# 14.net
KiCad netlist of a schematic drawn in EasyEDA Pro
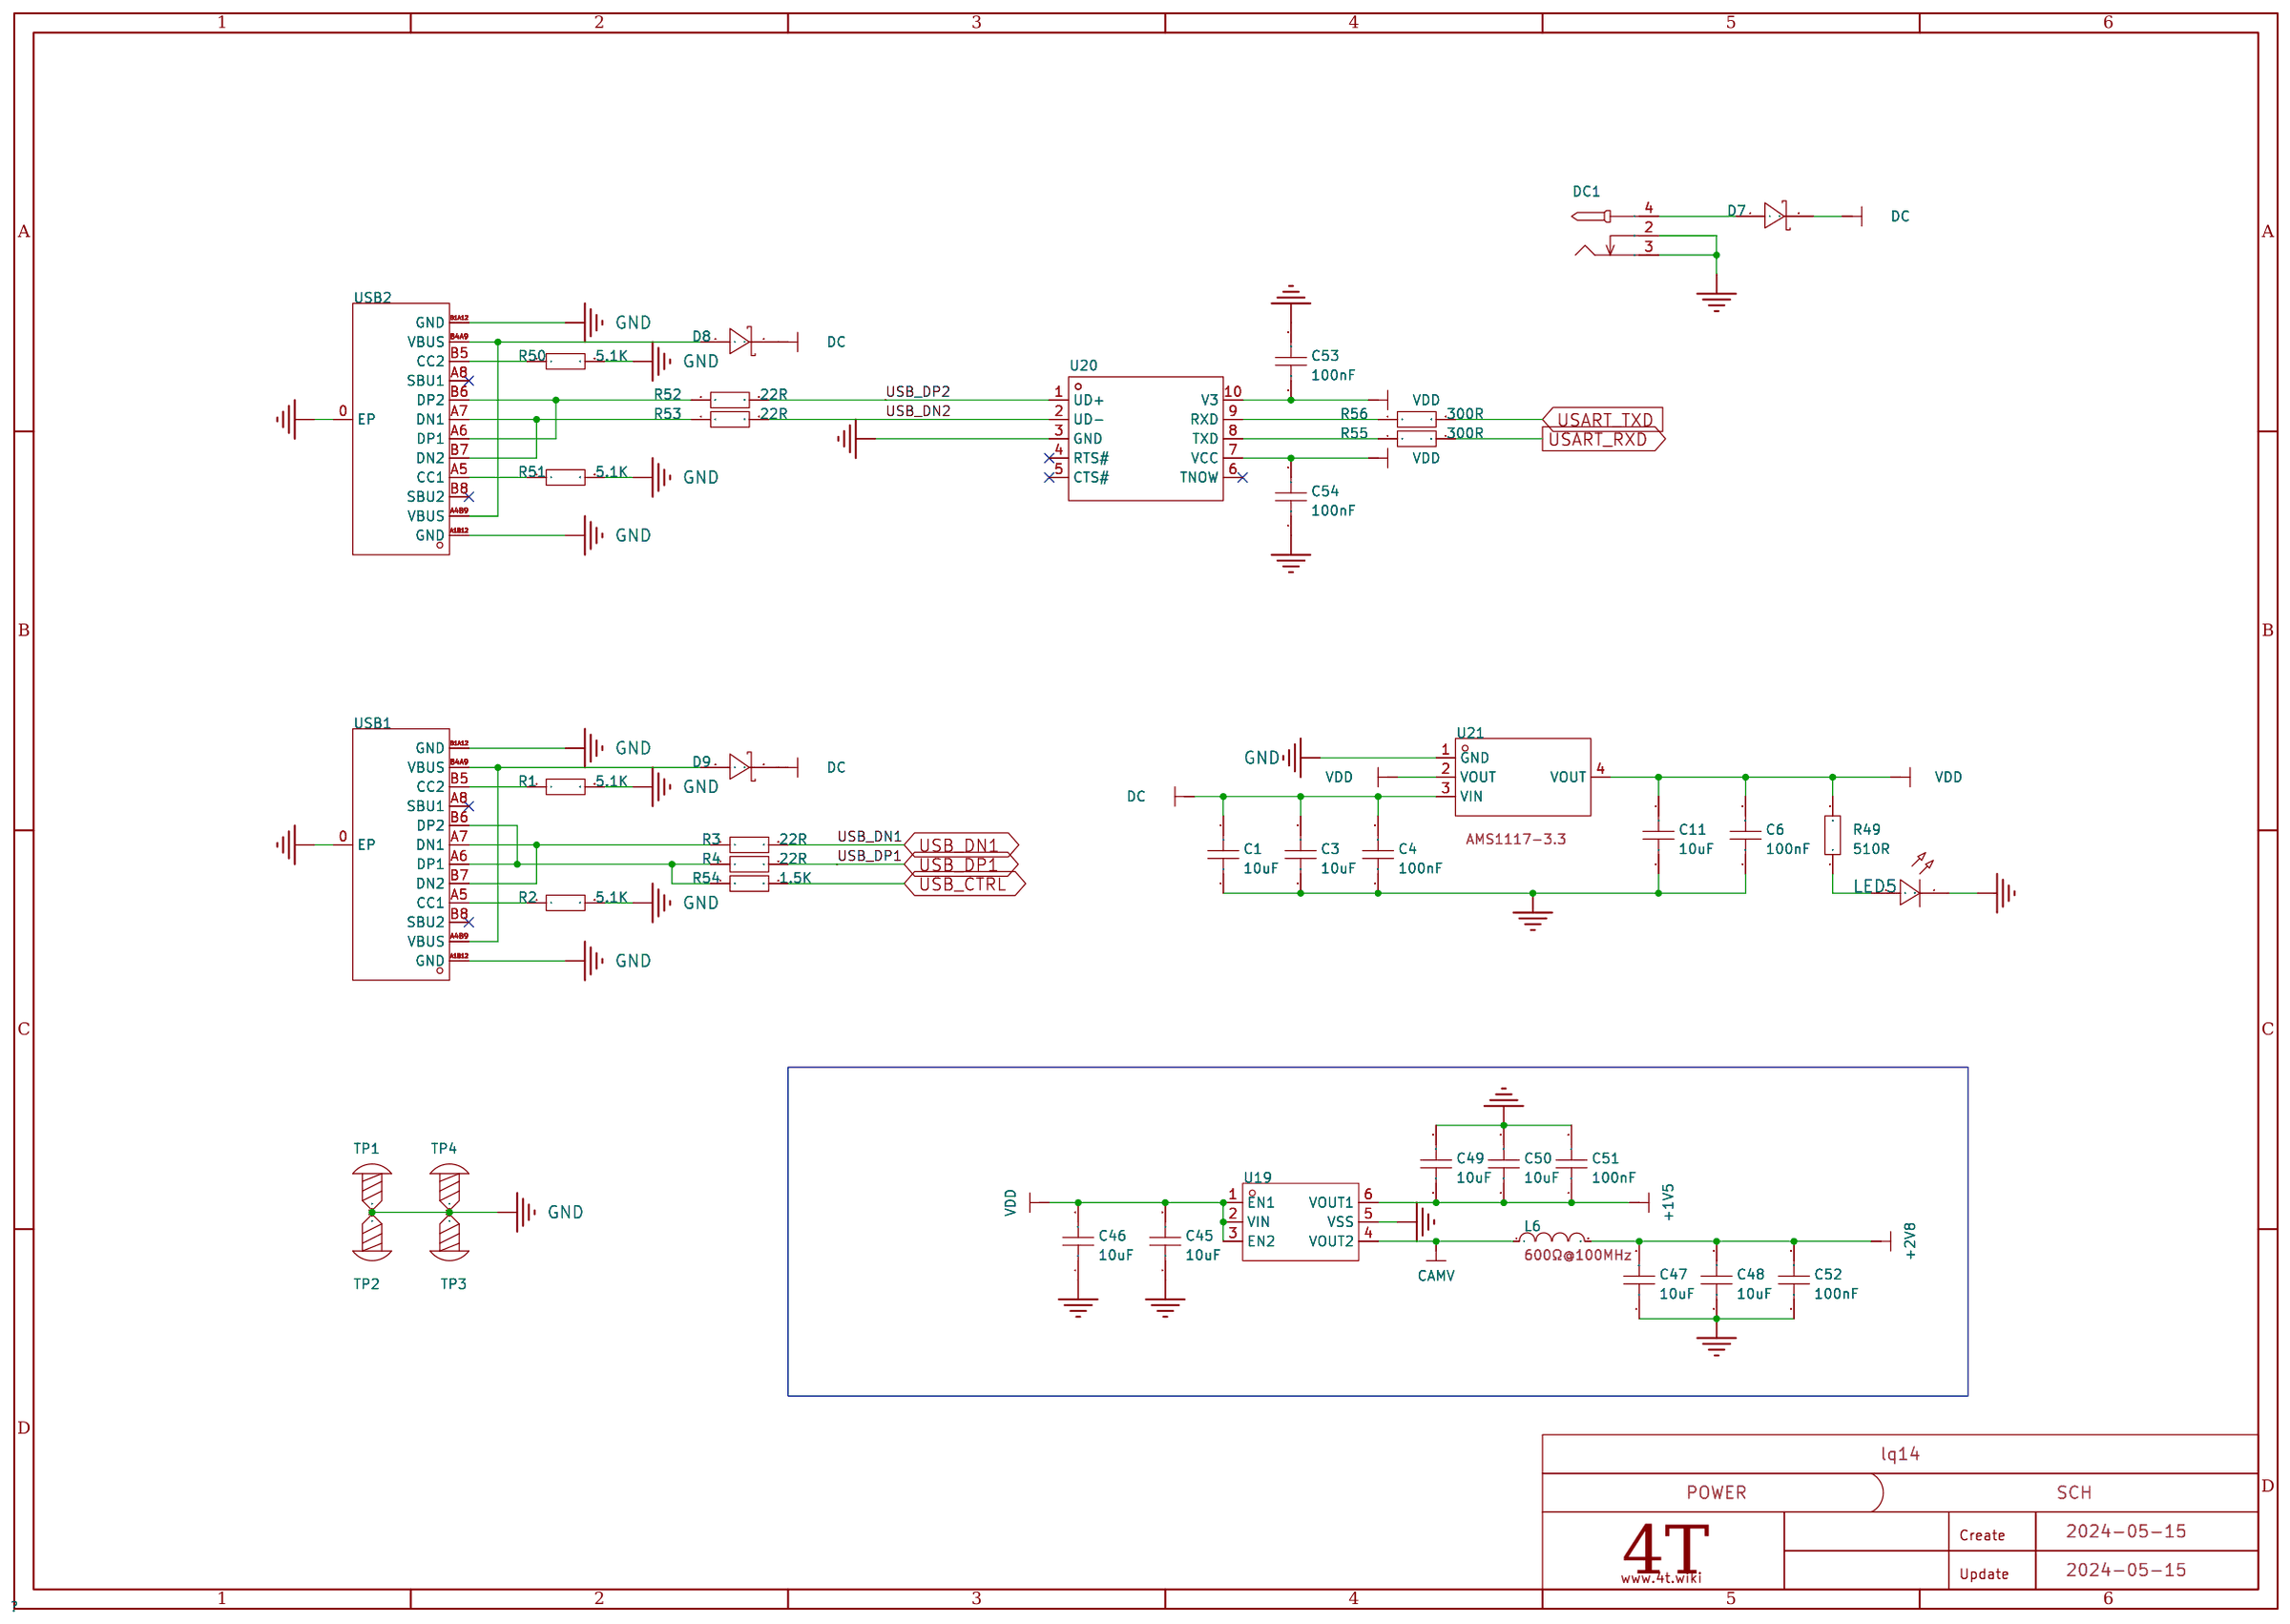
[diagram p0: POWER]
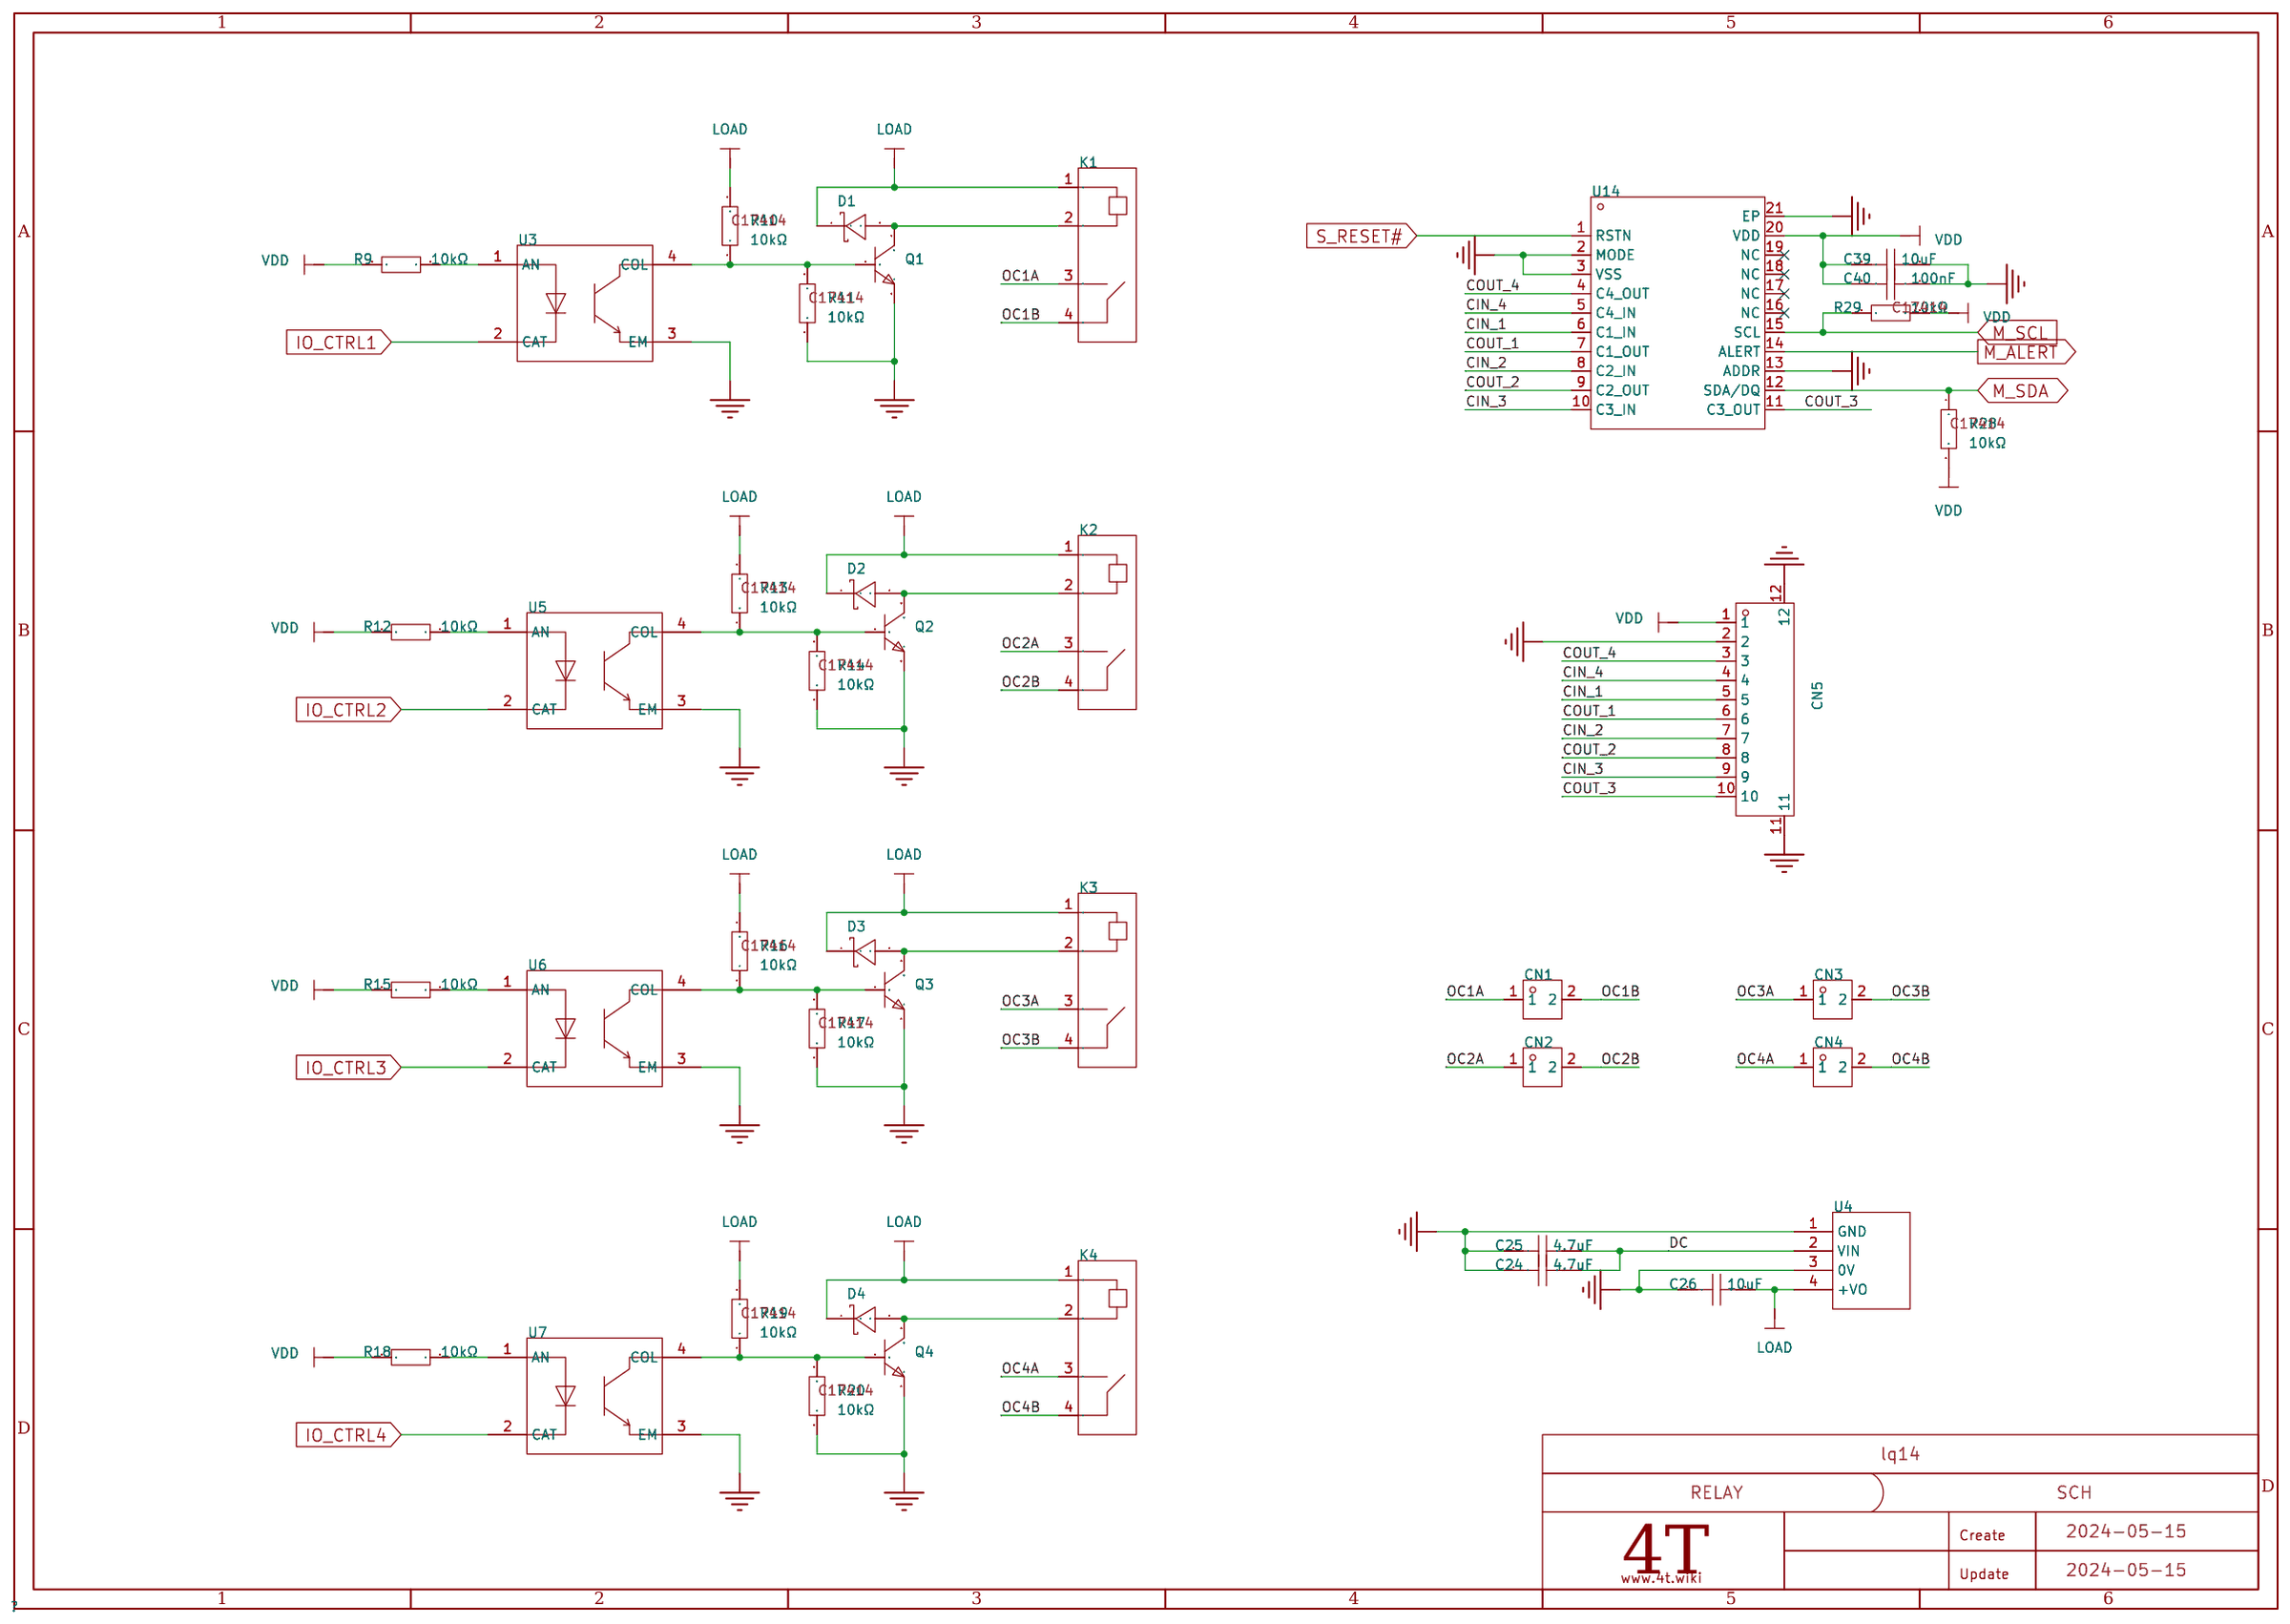
[diagram p1: RELAY]
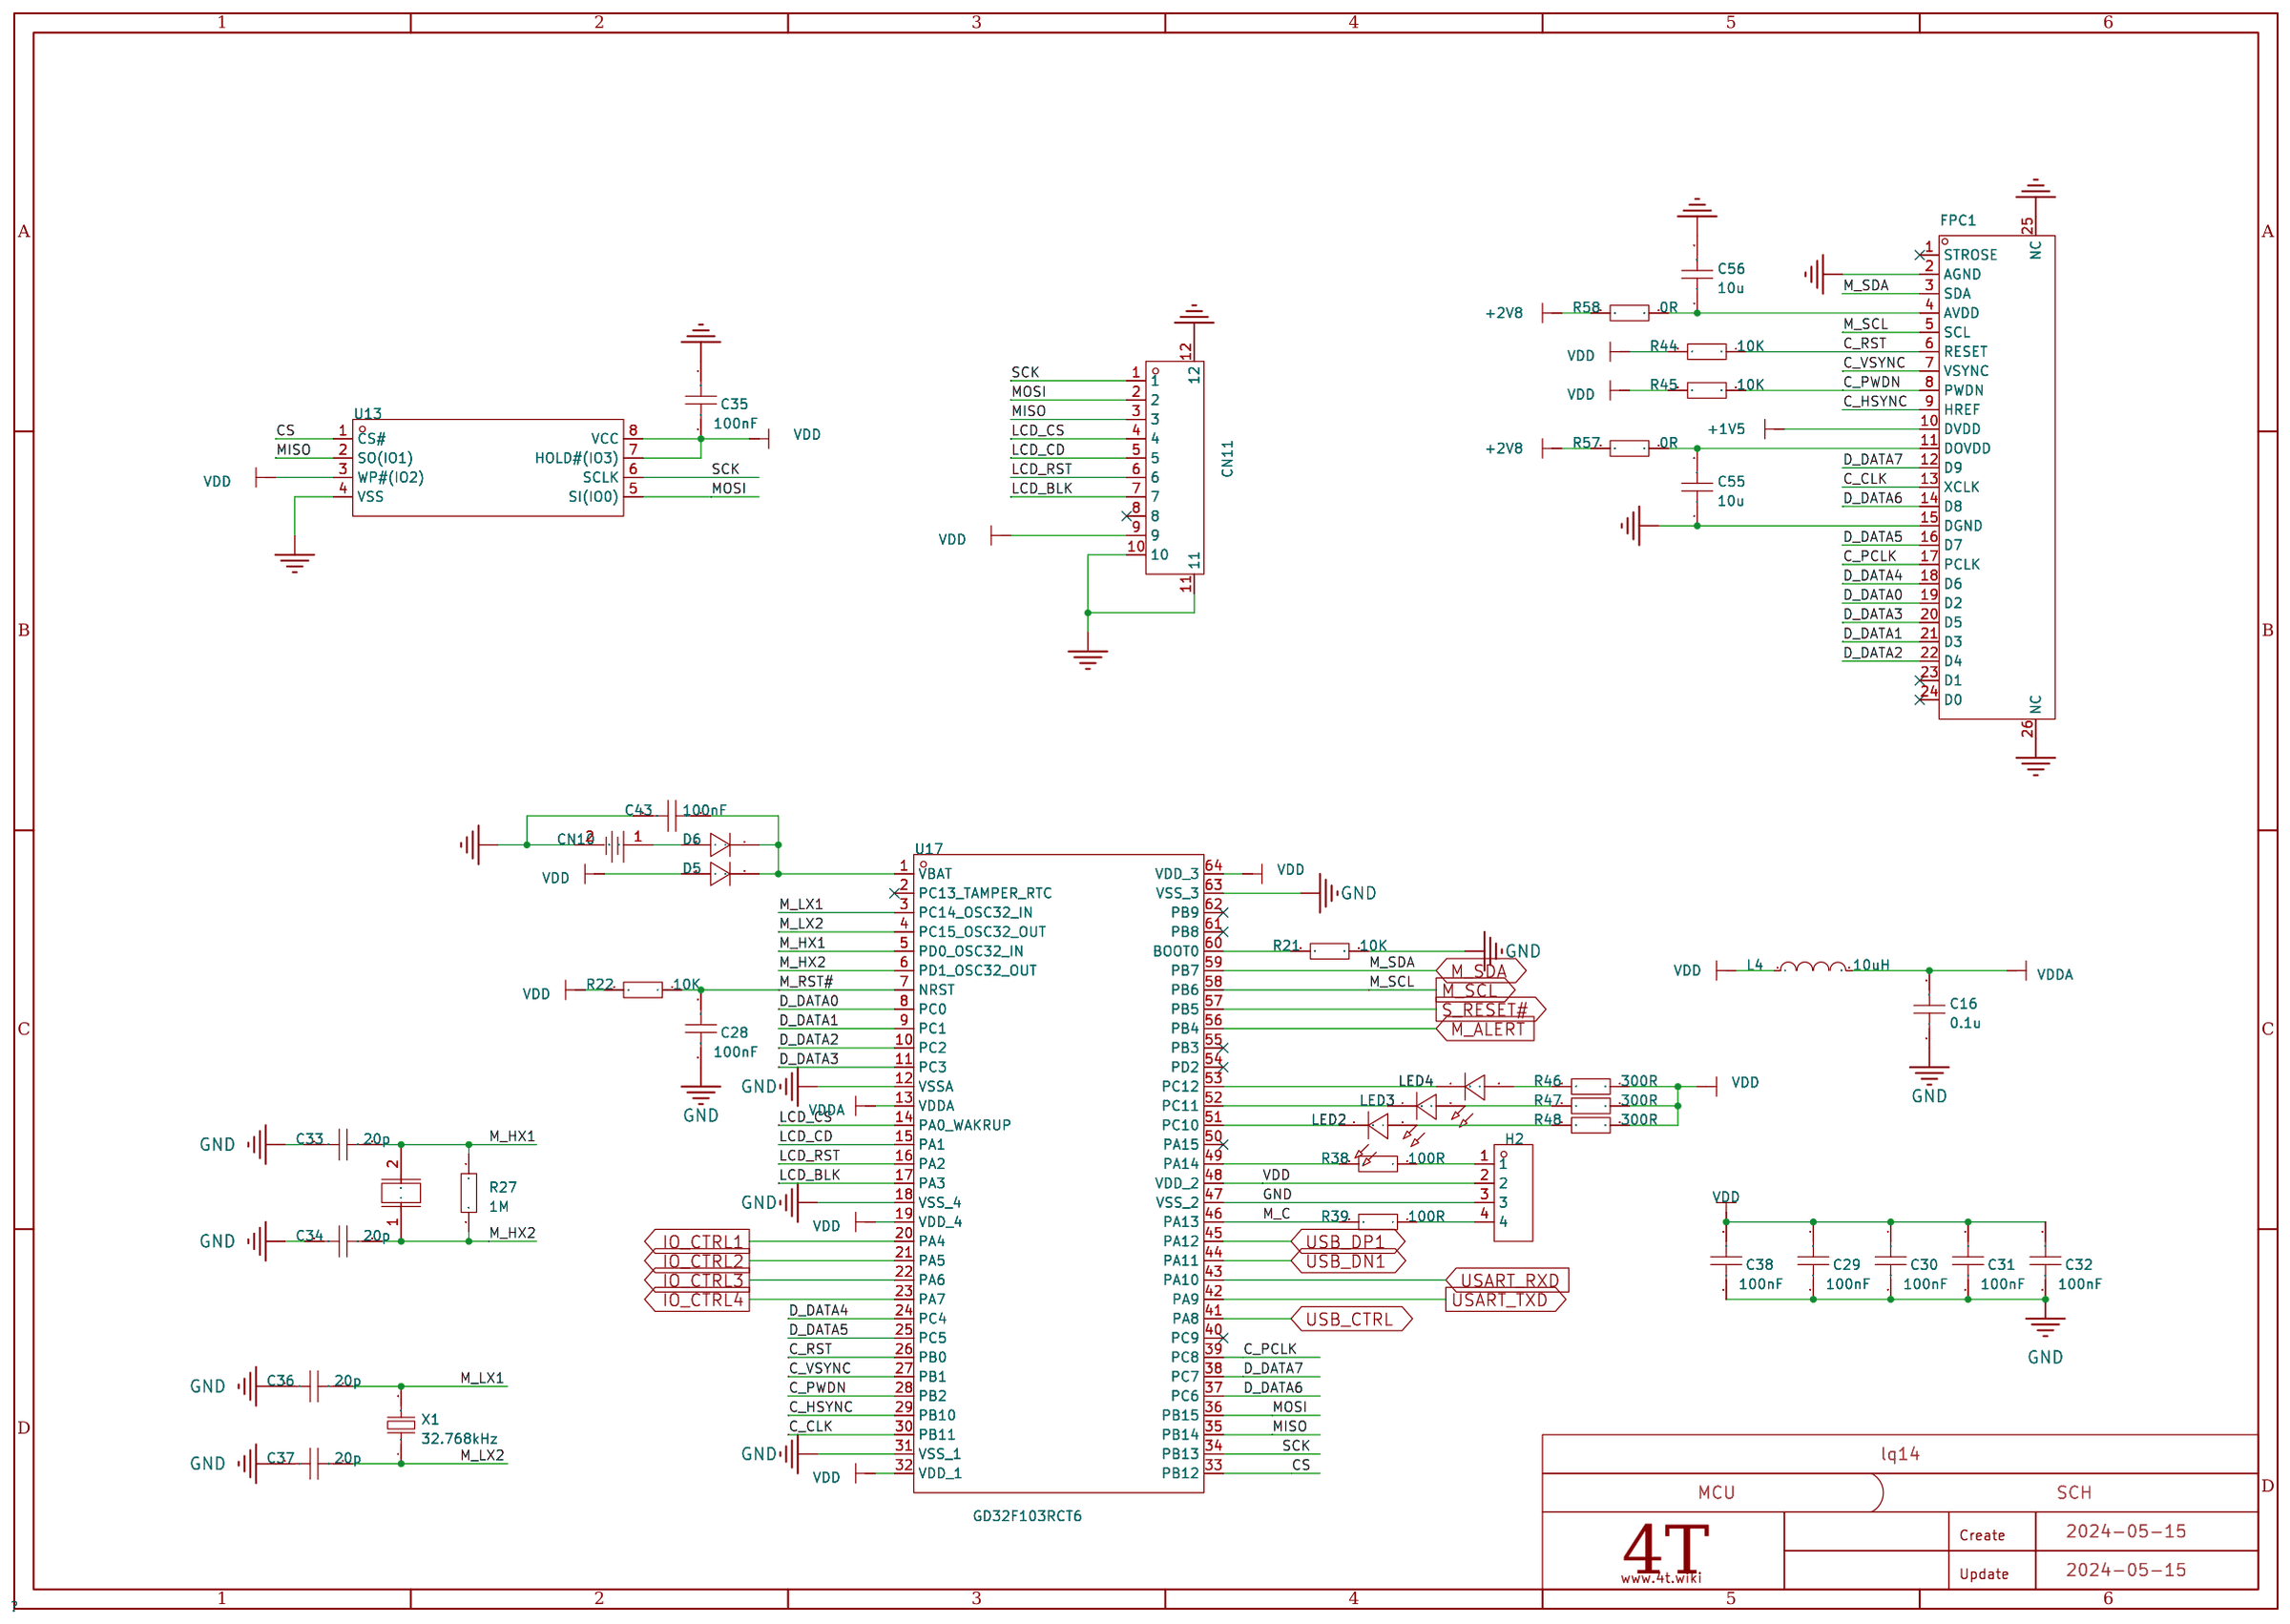
[diagram p2: MCU]

(export (version "E")
  (design (tool "Eeschema 10.0.6"))
  (components
    (comp (ref "C1")
      (value "10uF")
      (footprint "easyedapro:C0805")
      (description "容值:100nF;精度:±10%;额定电压:50V;温度系数:X7R;")
      (libsource (lib "easyedapro") (part "C1210X7R475K630NT"))
    )
    (comp (ref "C3")
      (value "10uF")
      (footprint "easyedapro:C0805")
      (description "容值:100nF;精度:±10%;额定电压:50V;温度系数:X7R;")
      (libsource (lib "easyedapro") (part "C1210X7R475K630NT"))
    )
    (comp (ref "C4")
      (value "100nF")
      (footprint "easyedapro:C0805")
      (description "容值:100nF;精度:±10%;额定电压:50V;温度系数:X7R;")
      (libsource (lib "easyedapro") (part "C1210X7R475K630NT"))
    )
    (comp (ref "C6")
      (value "100nF")
      (footprint "easyedapro:C0805")
      (description "容值:100nF;精度:±10%;额定电压:50V;温度系数:X7R;")
      (libsource (lib "easyedapro") (part "C1210X7R475K630NT"))
    )
    (comp (ref "C11")
      (value "10uF")
      (footprint "easyedapro:C0805")
      (description "容值:100nF;精度:±10%;额定电压:50V;温度系数:X7R;")
      (libsource (lib "easyedapro") (part "C1210X7R475K630NT"))
    )
    (comp (ref "C45")
      (value "10uF")
      (footprint "easyedapro:C0805")
      (description "容值:100nF;精度:±10%;额定电压:50V;温度系数:X7R;")
      (libsource (lib "easyedapro") (part "C1210X7R475K630NT"))
    )
    (comp (ref "C46")
      (value "10uF")
      (footprint "easyedapro:C0805")
      (description "容值:100nF;精度:±10%;额定电压:50V;温度系数:X7R;")
      (libsource (lib "easyedapro") (part "C1210X7R475K630NT"))
    )
    (comp (ref "C47")
      (value "10uF")
      (footprint "easyedapro:C0805")
      (description "容值:100nF;精度:±10%;额定电压:50V;温度系数:X7R;")
      (libsource (lib "easyedapro") (part "C1210X7R475K630NT"))
    )
    (comp (ref "C48")
      (value "10uF")
      (footprint "easyedapro:C0805")
      (description "容值:100nF;精度:±10%;额定电压:50V;温度系数:X7R;")
      (libsource (lib "easyedapro") (part "C1210X7R475K630NT"))
    )
    (comp (ref "C49")
      (value "10uF")
      (footprint "easyedapro:C0805")
      (description "容值:100nF;精度:±10%;额定电压:50V;温度系数:X7R;")
      (libsource (lib "easyedapro") (part "C1210X7R475K630NT"))
    )
    (comp (ref "C50")
      (value "10uF")
      (footprint "easyedapro:C0805")
      (description "容值:100nF;精度:±10%;额定电压:50V;温度系数:X7R;")
      (libsource (lib "easyedapro") (part "C1210X7R475K630NT"))
    )
    (comp (ref "C51")
      (value "100nF")
      (footprint "easyedapro:C0805")
      (description "容值:100nF;精度:±10%;额定电压:50V;温度系数:X7R;")
      (libsource (lib "easyedapro") (part "C1210X7R475K630NT"))
    )
    (comp (ref "C52")
      (value "100nF")
      (footprint "easyedapro:C0805")
      (description "容值:100nF;精度:±10%;额定电压:50V;温度系数:X7R;")
      (libsource (lib "easyedapro") (part "C1210X7R475K630NT"))
    )
    (comp (ref "C53")
      (value "100nF")
      (footprint "easyedapro:C0805")
      (description "容值:100nF;精度:±10%;额定电压:50V;温度系数:X7R;")
      (libsource (lib "easyedapro") (part "C1210X7R475K630NT"))
    )
    (comp (ref "C54")
      (value "100nF")
      (footprint "easyedapro:C0805")
      (description "容值:100nF;精度:±10%;额定电压:50V;温度系数:X7R;")
      (libsource (lib "easyedapro") (part "C1210X7R475K630NT"))
    )
    (comp (ref "D7")
      (value "SS34")
      (footprint "easyedapro:SMA_L4.3-W2.6-LS5.0-RD")
      (libsource (lib "easyedapro") (part "SS34_C9900023345"))
    )
    (comp (ref "D8")
      (value "SS34")
      (footprint "easyedapro:SMA_L4.3-W2.6-LS5.0-RD")
      (libsource (lib "easyedapro") (part "SS34_C9900023345"))
    )
    (comp (ref "D9")
      (value "SS34")
      (footprint "easyedapro:SMA_L4.3-W2.6-LS5.0-RD")
      (libsource (lib "easyedapro") (part "SS34_C9900023345"))
    )
    (comp (ref "DC1")
      (value "~")
      (footprint "easyedapro:DC-2.0")
      (libsource (lib "easyedapro") (part "DC电源接口"))
    )
    (comp (ref "L6")
      (value "BLM18AG601SN1D")
      (footprint "easyedapro:L0603")
      (description "标称阻抗@测试频率:600Ω@100MHz;误差:±25%;直流电阻(RDC):380mΩ;额定电流:500mA;电路数:1;")
      (fields (field (name "Manufacturer") "muRata(村田)") (field (name "Impedance @ Frequency") "600Ω@100MHz"))
      (libsource (lib "easyedapro") (part "BLM18AG601SN1D"))
    )
    (comp (ref "LED5")
      (value "~")
      (footprint "easyedapro:LED_0805")
      (libsource (lib "easyedapro") (part "LED_R"))
    )
    (comp (ref "R1") (value "5.1K") (footprint "easyedapro:R0805") (libsource (lib "easyedapro") (part "电阻")))
    (comp (ref "R2") (value "5.1K") (footprint "easyedapro:R0805") (libsource (lib "easyedapro") (part "电阻")))
    (comp (ref "R3") (value "22R") (footprint "easyedapro:R0805") (libsource (lib "easyedapro") (part "电阻")))
    (comp (ref "R4") (value "22R") (footprint "easyedapro:R0805") (libsource (lib "easyedapro") (part "电阻")))
    (comp (ref "R49")
      (value "510R")
      (footprint "easyedapro:R0805")
      (libsource (lib "easyedapro") (part "电阻"))
    )
    (comp (ref "R50")
      (value "5.1K")
      (footprint "easyedapro:R0805")
      (libsource (lib "easyedapro") (part "电阻"))
    )
    (comp (ref "R51")
      (value "5.1K")
      (footprint "easyedapro:R0805")
      (libsource (lib "easyedapro") (part "电阻"))
    )
    (comp (ref "R52") (value "22R") (footprint "easyedapro:R0805") (libsource (lib "easyedapro") (part "电阻")))
    (comp (ref "R53") (value "22R") (footprint "easyedapro:R0805") (libsource (lib "easyedapro") (part "电阻")))
    (comp (ref "R54")
      (value "1.5K")
      (footprint "easyedapro:R0805")
      (libsource (lib "easyedapro") (part "电阻"))
    )
    (comp (ref "R55")
      (value "300R")
      (footprint "easyedapro:R0805")
      (libsource (lib "easyedapro") (part "电阻"))
    )
    (comp (ref "R56")
      (value "300R")
      (footprint "easyedapro:R0805")
      (libsource (lib "easyedapro") (part "电阻"))
    )
    (comp (ref "TP1") (value "~") (footprint "easyedapro:M3螺丝") (libsource (lib "easyedapro") (part "螺丝孔")))
    (comp (ref "TP2") (value "~") (footprint "easyedapro:M3螺丝") (libsource (lib "easyedapro") (part "螺丝孔")))
    (comp (ref "TP3") (value "~") (footprint "easyedapro:M3螺丝") (libsource (lib "easyedapro") (part "螺丝孔")))
    (comp (ref "TP4") (value "~") (footprint "easyedapro:M3螺丝") (libsource (lib "easyedapro") (part "螺丝孔")))
    (comp (ref "U19") (value "~") (libsource (lib "easyedapro") (part "DPV")))
    (comp (ref "U20")
      (value "CH340E")
      (footprint "easyedapro:MSOP-10_L3.0-W3.0-P0.50-LS5.0-BL")
      (description "应用功能:收发器;接口协议:USB 2.0;数据速率:2Mbps;")
      (fields (field (name "Manufacturer") "WCH(南京沁恒)"))
      (libsource (lib "easyedapro") (part "CH340E"))
    )
    (comp (ref "U21")
      (value "AMS1117-3.3")
      (footprint "easyedapro:SOT-223-3_L6.5-W3.4-P2.30-LS7.0-BR")
      (description "输出类型:固定;输出极性:正;最大输入电压:-;输出电压:3.3V;输出电流:1A;电源纹波抑制比(PSRR):72dB@(120Hz);")
      (fields (field (name "Manufacturer Part") "AMS1117-3.3") (field (name "Manufacturer") "AMS"))
      (libsource (lib "easyedapro") (part "AMS1117-3.3"))
    )
    (comp (ref "USB1")
      (value "CQ-USB- TYPE-C 16P母座四脚插板有柱")
      (footprint "easyedapro:USB-C-SMD_CQ-USB-TYPE-C")
      (libsource (lib "easyedapro") (part "CQ-USB- TYPE-C 16P母座四脚插板有柱"))
    )
    (comp (ref "USB2")
      (value "CQ-USB- TYPE-C 16P母座四脚插板有柱")
      (footprint "easyedapro:USB-C-SMD_CQ-USB-TYPE-C")
      (libsource (lib "easyedapro") (part "CQ-USB- TYPE-C 16P母座四脚插板有柱"))
    )
    (comp (ref "C24")
      (value "4.7uF")
      (footprint "easyedapro:C0805")
      (libsource (lib "easyedapro") (part "CapAcitance"))
    )
    (comp (ref "C25")
      (value "4.7uF")
      (footprint "easyedapro:C0805")
      (libsource (lib "easyedapro") (part "CapAcitance"))
    )
    (comp (ref "C26")
      (value "10uF")
      (footprint "easyedapro:C0805")
      (libsource (lib "easyedapro") (part "CapAcitance"))
    )
    (comp (ref "C39")
      (value "10uF")
      (footprint "easyedapro:C0805")
      (libsource (lib "easyedapro") (part "CapAcitance"))
    )
    (comp (ref "C40")
      (value "100nF")
      (footprint "easyedapro:C0805")
      (libsource (lib "easyedapro") (part "CapAcitance"))
    )
    (comp (ref "CN1")
      (value "KF128L-5.08-2P 蓝色")
      (footprint "easyedapro:TH_KF128L-5.08-2P")
      (libsource (lib "easyedapro") (part "KF128L-5.08-2P 蓝色"))
    )
    (comp (ref "CN2")
      (value "KF128L-5.08-2P 蓝色")
      (footprint "easyedapro:TH_KF128L-5.08-2P")
      (libsource (lib "easyedapro") (part "KF128L-5.08-2P 蓝色"))
    )
    (comp (ref "CN3")
      (value "KF128L-5.08-2P 蓝色")
      (footprint "easyedapro:TH_KF128L-5.08-2P")
      (libsource (lib "easyedapro") (part "KF128L-5.08-2P 蓝色"))
    )
    (comp (ref "CN4")
      (value "KF128L-5.08-2P 蓝色")
      (footprint "easyedapro:TH_KF128L-5.08-2P")
      (libsource (lib "easyedapro") (part "KF128L-5.08-2P 蓝色"))
    )
    (comp (ref "CN5")
      (value "KH-A1251WF-10A")
      (fields (field (name "Manufacturer") "kinghelm(金航标)"))
      (libsource (lib "easyedapro") (part "KH-FPC0.5-H1.0SMT-10P-QCHF"))
    )
    (comp (ref "D1")
      (value "SS14")
      (footprint "easyedapro:SMA_L4.2-W2.6-LS5.3-RD")
      (description "二极管配置:独立式;直流反向耐压(Vr):40V;平均整流电流(Io):1A;正向压降(Vf):550mV@1A;反向电流(Ir):500uA@40V;")
      (fields (field (name "Manufacturer") "MDD"))
      (libsource (lib "easyedapro") (part "SS14"))
    )
    (comp (ref "D2")
      (value "SS14")
      (footprint "easyedapro:SMA_L4.2-W2.6-LS5.3-RD")
      (description "二极管配置:独立式;直流反向耐压(Vr):40V;平均整流电流(Io):1A;正向压降(Vf):550mV@1A;反向电流(Ir):500uA@40V;")
      (fields (field (name "Manufacturer") "MDD"))
      (libsource (lib "easyedapro") (part "SS14"))
    )
    (comp (ref "D3")
      (value "SS14")
      (footprint "easyedapro:SMA_L4.2-W2.6-LS5.3-RD")
      (description "二极管配置:独立式;直流反向耐压(Vr):40V;平均整流电流(Io):1A;正向压降(Vf):550mV@1A;反向电流(Ir):500uA@40V;")
      (fields (field (name "Manufacturer") "MDD"))
      (libsource (lib "easyedapro") (part "SS14"))
    )
    (comp (ref "D4")
      (value "SS14")
      (footprint "easyedapro:SMA_L4.2-W2.6-LS5.3-RD")
      (description "二极管配置:独立式;直流反向耐压(Vr):40V;平均整流电流(Io):1A;正向压降(Vf):550mV@1A;反向电流(Ir):500uA@40V;")
      (fields (field (name "Manufacturer") "MDD"))
      (libsource (lib "easyedapro") (part "SS14"))
    )
    (comp (ref "K1")
      (value "HF49FD/012-1H12")
      (footprint "easyedapro:RELAY-TH_HF49FD-XXX-1H12-XXX")
      (description "线圈电压:12V;线圈类型:非极化-单线圈;触点形式:一组常开:1A(单刀单掷-常开);最大切换电流:5A;触点材料:AgNi;")
      (fields (field (name "Manufacturer") "HF(宏发)"))
      (libsource (lib "easyedapro") (part "HF49FD/012-1H12"))
    )
    (comp (ref "K2")
      (value "HF49FD/012-1H12")
      (footprint "easyedapro:RELAY-TH_HF49FD-XXX-1H12-XXX")
      (description "线圈电压:12V;线圈类型:非极化-单线圈;触点形式:一组常开:1A(单刀单掷-常开);最大切换电流:5A;触点材料:AgNi;")
      (fields (field (name "Manufacturer") "HF(宏发)"))
      (libsource (lib "easyedapro") (part "HF49FD/012-1H12"))
    )
    (comp (ref "K3")
      (value "HF49FD/012-1H12")
      (footprint "easyedapro:RELAY-TH_HF49FD-XXX-1H12-XXX")
      (description "线圈电压:12V;线圈类型:非极化-单线圈;触点形式:一组常开:1A(单刀单掷-常开);最大切换电流:5A;触点材料:AgNi;")
      (fields (field (name "Manufacturer") "HF(宏发)"))
      (libsource (lib "easyedapro") (part "HF49FD/012-1H12"))
    )
    (comp (ref "K4")
      (value "HF49FD/012-1H12")
      (footprint "easyedapro:RELAY-TH_HF49FD-XXX-1H12-XXX")
      (description "线圈电压:12V;线圈类型:非极化-单线圈;触点形式:一组常开:1A(单刀单掷-常开);最大切换电流:5A;触点材料:AgNi;")
      (fields (field (name "Manufacturer") "HF(宏发)"))
      (libsource (lib "easyedapro") (part "HF49FD/012-1H12"))
    )
    (comp (ref "Q1")
      (value "SS8050")
      (footprint "easyedapro:SOT-23-3_L2.9-W1.3-P1.90-LS2.4-BR")
      (description "晶体管类型:NPN;集射极击穿电压(Vceo):25V;集电极电流(Ic):1.5A;功率(Pd):300mW;直流电流增益(hFE@Ic,Vce):200@100mA,1V;")
      (fields (field (name "Manufacturer") "CJ(江苏长电/长晶)"))
      (libsource (lib "easyedapro") (part "SS8050_C2150"))
    )
    (comp (ref "Q2")
      (value "SS8050")
      (footprint "easyedapro:SOT-23-3_L2.9-W1.3-P1.90-LS2.4-BR")
      (description "晶体管类型:NPN;集射极击穿电压(Vceo):25V;集电极电流(Ic):1.5A;功率(Pd):300mW;直流电流增益(hFE@Ic,Vce):200@100mA,1V;")
      (fields (field (name "Manufacturer") "CJ(江苏长电/长晶)"))
      (libsource (lib "easyedapro") (part "SS8050_C2150"))
    )
    (comp (ref "Q3")
      (value "SS8050")
      (footprint "easyedapro:SOT-23-3_L2.9-W1.3-P1.90-LS2.4-BR")
      (description "晶体管类型:NPN;集射极击穿电压(Vceo):25V;集电极电流(Ic):1.5A;功率(Pd):300mW;直流电流增益(hFE@Ic,Vce):200@100mA,1V;")
      (fields (field (name "Manufacturer") "CJ(江苏长电/长晶)"))
      (libsource (lib "easyedapro") (part "SS8050_C2150"))
    )
    (comp (ref "Q4")
      (value "SS8050")
      (footprint "easyedapro:SOT-23-3_L2.9-W1.3-P1.90-LS2.4-BR")
      (description "晶体管类型:NPN;集射极击穿电压(Vceo):25V;集电极电流(Ic):1.5A;功率(Pd):300mW;直流电流增益(hFE@Ic,Vce):200@100mA,1V;")
      (fields (field (name "Manufacturer") "CJ(江苏长电/长晶)"))
      (libsource (lib "easyedapro") (part "SS8050_C2150"))
    )
    (comp (ref "R9")
      (value "10kΩ")
      (footprint "easyedapro:R0805")
      (description "电阻类型:厚膜电阻;阻值:10kΩ;精度:±1%;功率:125mW;")
      (fields
        (field (name "Manufacturer Part") "0805W8F1002T5E")
        (field (name "Manufacturer") "UNI-ROYAL(厚声)")
        (field (name "Supplier Part") "C17414")
      )
      (libsource (lib "easyedapro") (part "0805W8F1002T5E"))
    )
    (comp (ref "R10")
      (value "10kΩ")
      (footprint "easyedapro:R0805")
      (description "电阻类型:厚膜电阻;阻值:10kΩ;精度:±1%;功率:125mW;")
      (fields
        (field (name "Manufacturer Part") "0805W8F1002T5E")
        (field (name "Manufacturer") "UNI-ROYAL(厚声)")
        (field (name "Supplier Part") "C17414")
      )
      (libsource (lib "easyedapro") (part "0805W8F1002T5E"))
    )
    (comp (ref "R11")
      (value "10kΩ")
      (footprint "easyedapro:R0805")
      (description "电阻类型:厚膜电阻;阻值:10kΩ;精度:±1%;功率:125mW;")
      (fields
        (field (name "Manufacturer Part") "0805W8F1002T5E")
        (field (name "Manufacturer") "UNI-ROYAL(厚声)")
        (field (name "Supplier Part") "C17414")
      )
      (libsource (lib "easyedapro") (part "0805W8F1002T5E"))
    )
    (comp (ref "R12")
      (value "10kΩ")
      (footprint "easyedapro:R0805")
      (description "电阻类型:厚膜电阻;阻值:10kΩ;精度:±1%;功率:125mW;")
      (fields
        (field (name "Manufacturer Part") "0805W8F1002T5E")
        (field (name "Manufacturer") "UNI-ROYAL(厚声)")
        (field (name "Supplier Part") "C17414")
      )
      (libsource (lib "easyedapro") (part "0805W8F1002T5E"))
    )
    (comp (ref "R13")
      (value "10kΩ")
      (footprint "easyedapro:R0805")
      (description "电阻类型:厚膜电阻;阻值:10kΩ;精度:±1%;功率:125mW;")
      (fields
        (field (name "Manufacturer Part") "0805W8F1002T5E")
        (field (name "Manufacturer") "UNI-ROYAL(厚声)")
        (field (name "Supplier Part") "C17414")
      )
      (libsource (lib "easyedapro") (part "0805W8F1002T5E"))
    )
    (comp (ref "R14")
      (value "10kΩ")
      (footprint "easyedapro:R0805")
      (description "电阻类型:厚膜电阻;阻值:10kΩ;精度:±1%;功率:125mW;")
      (fields
        (field (name "Manufacturer Part") "0805W8F1002T5E")
        (field (name "Manufacturer") "UNI-ROYAL(厚声)")
        (field (name "Supplier Part") "C17414")
      )
      (libsource (lib "easyedapro") (part "0805W8F1002T5E"))
    )
    (comp (ref "R15")
      (value "10kΩ")
      (footprint "easyedapro:R0805")
      (description "电阻类型:厚膜电阻;阻值:10kΩ;精度:±1%;功率:125mW;")
      (fields
        (field (name "Manufacturer Part") "0805W8F1002T5E")
        (field (name "Manufacturer") "UNI-ROYAL(厚声)")
        (field (name "Supplier Part") "C17414")
      )
      (libsource (lib "easyedapro") (part "0805W8F1002T5E"))
    )
    (comp (ref "R16")
      (value "10kΩ")
      (footprint "easyedapro:R0805")
      (description "电阻类型:厚膜电阻;阻值:10kΩ;精度:±1%;功率:125mW;")
      (fields
        (field (name "Manufacturer Part") "0805W8F1002T5E")
        (field (name "Manufacturer") "UNI-ROYAL(厚声)")
        (field (name "Supplier Part") "C17414")
      )
      (libsource (lib "easyedapro") (part "0805W8F1002T5E"))
    )
    (comp (ref "R17")
      (value "10kΩ")
      (footprint "easyedapro:R0805")
      (description "电阻类型:厚膜电阻;阻值:10kΩ;精度:±1%;功率:125mW;")
      (fields
        (field (name "Manufacturer Part") "0805W8F1002T5E")
        (field (name "Manufacturer") "UNI-ROYAL(厚声)")
        (field (name "Supplier Part") "C17414")
      )
      (libsource (lib "easyedapro") (part "0805W8F1002T5E"))
    )
    (comp (ref "R18")
      (value "10kΩ")
      (footprint "easyedapro:R0805")
      (description "电阻类型:厚膜电阻;阻值:10kΩ;精度:±1%;功率:125mW;")
      (fields
        (field (name "Manufacturer Part") "0805W8F1002T5E")
        (field (name "Manufacturer") "UNI-ROYAL(厚声)")
        (field (name "Supplier Part") "C17414")
      )
      (libsource (lib "easyedapro") (part "0805W8F1002T5E"))
    )
    (comp (ref "R19")
      (value "10kΩ")
      (footprint "easyedapro:R0805")
      (description "电阻类型:厚膜电阻;阻值:10kΩ;精度:±1%;功率:125mW;")
      (fields
        (field (name "Manufacturer Part") "0805W8F1002T5E")
        (field (name "Manufacturer") "UNI-ROYAL(厚声)")
        (field (name "Supplier Part") "C17414")
      )
      (libsource (lib "easyedapro") (part "0805W8F1002T5E"))
    )
    (comp (ref "R20")
      (value "10kΩ")
      (footprint "easyedapro:R0805")
      (description "电阻类型:厚膜电阻;阻值:10kΩ;精度:±1%;功率:125mW;")
      (fields
        (field (name "Manufacturer Part") "0805W8F1002T5E")
        (field (name "Manufacturer") "UNI-ROYAL(厚声)")
        (field (name "Supplier Part") "C17414")
      )
      (libsource (lib "easyedapro") (part "0805W8F1002T5E"))
    )
    (comp (ref "R28")
      (value "10kΩ")
      (footprint "easyedapro:R0805")
      (description "电阻类型:厚膜电阻;阻值:10kΩ;精度:±1%;功率:125mW;")
      (fields
        (field (name "Manufacturer Part") "0805W8F1002T5E")
        (field (name "Manufacturer") "UNI-ROYAL(厚声)")
        (field (name "Supplier Part") "C17414")
      )
      (libsource (lib "easyedapro") (part "0805W8F1002T5E"))
    )
    (comp (ref "R29")
      (value "10kΩ")
      (footprint "easyedapro:R0805")
      (description "电阻类型:厚膜电阻;阻值:10kΩ;精度:±1%;功率:125mW;")
      (fields
        (field (name "Manufacturer Part") "0805W8F1002T5E")
        (field (name "Manufacturer") "UNI-ROYAL(厚声)")
        (field (name "Supplier Part") "C17414")
      )
      (libsource (lib "easyedapro") (part "0805W8F1002T5E"))
    )
    (comp (ref "U3")
      (value "TLP521-1XSM")
      (footprint "easyedapro:SMD-4_L4.6-W6.5-P2.54-LS10.2-BL")
      (fields (field (name "Manufacturer") "ISOCOM(英国安数光)"))
      (libsource (lib "easyedapro") (part "TLP521-1XSM"))
    )
    (comp (ref "U4")
      (value "B0505S-1WR3")
      (footprint "easyedapro:PWRM-TH_B0503S-1WR3")
      (description "电压输出的组数:-;最大输入电压:-;输出电压:-;输出电流（最大值/满载）:-;")
      (fields (field (name "Manufacturer") "Taisko(台思科)"))
      (libsource (lib "easyedapro") (part "B0505S-1WR3_C382179"))
    )
    (comp (ref "U5")
      (value "TLP521-1XSM")
      (footprint "easyedapro:SMD-4_L4.6-W6.5-P2.54-LS10.2-BL")
      (fields (field (name "Manufacturer") "ISOCOM(英国安数光)"))
      (libsource (lib "easyedapro") (part "TLP521-1XSM"))
    )
    (comp (ref "U6")
      (value "TLP521-1XSM")
      (footprint "easyedapro:SMD-4_L4.6-W6.5-P2.54-LS10.2-BL")
      (fields (field (name "Manufacturer") "ISOCOM(英国安数光)"))
      (libsource (lib "easyedapro") (part "TLP521-1XSM"))
    )
    (comp (ref "U7")
      (value "TLP521-1XSM")
      (footprint "easyedapro:SMD-4_L4.6-W6.5-P2.54-LS10.2-BL")
      (fields (field (name "Manufacturer") "ISOCOM(英国安数光)"))
      (libsource (lib "easyedapro") (part "TLP521-1XSM"))
    )
    (comp (ref "U14")
      (value "MDC04")
      (footprint "easyedapro:QFN-20_L3.0-W3.0-P0.40-BL-EP1.7")
      (description "测量范围 0 ~119pF 接口 I?C 测量速度 3 ~20ms 分辨率 0.1fF 供电电压    2.0V~5.5V 平均功耗 4.5μA 通道数 4")
      (fields (field (name "Manufacturer") "Mysentech(敏源传感)"))
      (libsource (lib "easyedapro") (part "MDC04"))
    )
    (comp (ref "C16")
      (value "0.1u")
      (footprint "easyedapro:C0805")
      (description "容值:100nF;精度:±10%;额定电压:50V;温度系数:X7R;")
      (libsource (lib "easyedapro") (part "C1210X7R475K630NT"))
    )
    (comp (ref "C28")
      (value "100nF")
      (footprint "easyedapro:C0805")
      (libsource (lib "easyedapro") (part "CapAcitance"))
    )
    (comp (ref "C29")
      (value "100nF")
      (footprint "easyedapro:C0805")
      (libsource (lib "easyedapro") (part "CapAcitance"))
    )
    (comp (ref "C30")
      (value "100nF")
      (footprint "easyedapro:C0805")
      (libsource (lib "easyedapro") (part "CapAcitance"))
    )
    (comp (ref "C31")
      (value "100nF")
      (footprint "easyedapro:C0805")
      (libsource (lib "easyedapro") (part "CapAcitance"))
    )
    (comp (ref "C32")
      (value "100nF")
      (footprint "easyedapro:C0805")
      (libsource (lib "easyedapro") (part "CapAcitance"))
    )
    (comp (ref "C33")
      (value "20p")
      (footprint "easyedapro:C0805")
      (libsource (lib "easyedapro") (part "CapAcitance"))
    )
    (comp (ref "C34")
      (value "20p")
      (footprint "easyedapro:C0805")
      (libsource (lib "easyedapro") (part "CapAcitance"))
    )
    (comp (ref "C35")
      (value "100nF")
      (footprint "easyedapro:C0805")
      (libsource (lib "easyedapro") (part "CapAcitance"))
    )
    (comp (ref "C36")
      (value "20p")
      (footprint "easyedapro:C0805")
      (libsource (lib "easyedapro") (part "CapAcitance"))
    )
    (comp (ref "C37")
      (value "20p")
      (footprint "easyedapro:C0805")
      (libsource (lib "easyedapro") (part "CapAcitance"))
    )
    (comp (ref "C38")
      (value "100nF")
      (footprint "easyedapro:C0805")
      (libsource (lib "easyedapro") (part "CapAcitance"))
    )
    (comp (ref "C43")
      (value "100nF")
      (footprint "easyedapro:C0805")
      (libsource (lib "easyedapro") (part "CapAcitance"))
    )
    (comp (ref "C55")
      (value "10u")
      (footprint "easyedapro:C0805")
      (description "容值:100nF;精度:±10%;额定电压:50V;温度系数:X7R;")
      (libsource (lib "easyedapro") (part "C1210X7R475K630NT"))
    )
    (comp (ref "C56")
      (value "10u")
      (footprint "easyedapro:C0805")
      (description "容值:100nF;精度:±10%;额定电压:50V;温度系数:X7R;")
      (libsource (lib "easyedapro") (part "C1210X7R475K630NT"))
    )
    (comp (ref "CN10")
      (value "CR1220_B")
      (footprint "easyedapro:BAT-SMD_CR1220-2ZX")
      (libsource (lib "easyedapro") (part "CR1220_B"))
    )
    (comp (ref "CN11")
      (value "KH-A1251WF-10A")
      (fields (field (name "Manufacturer") "kinghelm(金航标)"))
      (libsource (lib "easyedapro") (part "KH-FPC0.5-H1.0SMT-10P-QCHF"))
    )
    (comp (ref "D5")
      (value "1N4148WS")
      (footprint "easyedapro:SOD-323_L1.8-W1.3-LS2.5-RD")
      (fields (field (name "Manufacturer") "CJ(江苏长电/长晶)"))
      (libsource (lib "easyedapro") (part "1N4148WS T4"))
    )
    (comp (ref "D6")
      (value "1N4148WS")
      (footprint "easyedapro:SOD-323_L1.8-W1.3-LS2.5-RD")
      (fields (field (name "Manufacturer") "CJ(江苏长电/长晶)"))
      (libsource (lib "easyedapro") (part "1N4148WS T4"))
    )
    (comp (ref "FPC1")
      (value "F-FPC0M24P-C310")
      (fields (field (name "Manufacturer") "Ckmtw(灿科盟)"))
      (libsource (lib "easyedapro") (part "OV2640"))
    )
    (comp (ref "H2")
      (value "2.54-1*4P母")
      (fields (field (name "Manufacturer") "BOOMELE(博穆精密)"))
      (libsource (lib "easyedapro") (part "2.54-1*4P母"))
    )
    (comp (ref "L4")
      (value "10uH")
      (footprint "easyedapro:L0805")
      (description "电感值:10uH;精度:±10%;额定电流:15mA;饱和电流(Isat):-;直流电阻(DCR):1.15Ω;")
      (libsource (lib "easyedapro") (part "SDFL2012S100KTF"))
    )
    (comp (ref "LED2")
      (value "~")
      (footprint "easyedapro:LED_0805")
      (libsource (lib "easyedapro") (part "LED_G"))
    )
    (comp (ref "LED3")
      (value "~")
      (footprint "easyedapro:LED_0805")
      (libsource (lib "easyedapro") (part "LED_G"))
    )
    (comp (ref "LED4")
      (value "~")
      (footprint "easyedapro:LED_0805")
      (libsource (lib "easyedapro") (part "LED_G"))
    )
    (comp (ref "R21") (value "10K") (footprint "easyedapro:R0805") (libsource (lib "easyedapro") (part "电阻")))
    (comp (ref "R22") (value "10K") (footprint "easyedapro:R0805") (libsource (lib "easyedapro") (part "电阻")))
    (comp (ref "R27") (value "1M") (footprint "easyedapro:R0805") (libsource (lib "easyedapro") (part "电阻")))
    (comp (ref "R38")
      (value "100R")
      (footprint "easyedapro:R0805")
      (libsource (lib "easyedapro") (part "电阻"))
    )
    (comp (ref "R39")
      (value "100R")
      (footprint "easyedapro:R0805")
      (libsource (lib "easyedapro") (part "电阻"))
    )
    (comp (ref "R44") (value "10K") (footprint "easyedapro:R0805") (libsource (lib "easyedapro") (part "电阻")))
    (comp (ref "R45") (value "10K") (footprint "easyedapro:R0805") (libsource (lib "easyedapro") (part "电阻")))
    (comp (ref "R46")
      (value "300R")
      (footprint "easyedapro:R0805")
      (libsource (lib "easyedapro") (part "电阻"))
    )
    (comp (ref "R47")
      (value "300R")
      (footprint "easyedapro:R0805")
      (libsource (lib "easyedapro") (part "电阻"))
    )
    (comp (ref "R48")
      (value "300R")
      (footprint "easyedapro:R0805")
      (libsource (lib "easyedapro") (part "电阻"))
    )
    (comp (ref "R57") (value "0R") (footprint "easyedapro:R0805") (libsource (lib "easyedapro") (part "电阻")))
    (comp (ref "R58") (value "0R") (footprint "easyedapro:R0805") (libsource (lib "easyedapro") (part "电阻")))
    (comp (ref "U12")
      (value "8M-5032-2P")
      (footprint "easyedapro:CRYSTAL-SMD_L5.0-W3.2")
      (libsource (lib "easyedapro") (part "8M-5032-2P"))
    )
    (comp (ref "U13")
      (value "GD25Q16CSAG-SOP8_208MIL")
      (footprint "easyedapro:SOP-8_L5.2-W5.3-P1.27-LS7.9-BL")
      (libsource (lib "easyedapro") (part "GD25Q16CSAG-SOP8_208MIL"))
    )
    (comp (ref "U17")
      (value "GD32F103RCT6")
      (footprint "easyedapro:LQFP-64_L10.0-W10.0-P0.50-LS12.0-BL")
      (description "CPU内核:ARM Cortex-M3;CPU最大主频:108MHz;程序存储容量:256KB;程序存储器类型:FLASH;RAM总容量:48KB;GPIO端口数量:51;")
      (fields (field (name "Manufacturer") "GigaDevice(兆易创新)"))
      (libsource (lib "easyedapro") (part "GD32F103RCT6"))
    )
    (comp (ref "X1")
      (value "32.768kHz")
      (footprint "easyedapro:FC-135R_L3.2-W1.5")
      (description "频率:32.768kHz;频率公差:±20ppm;负载电容:12.5pF;")
      (fields (field (name "Manufacturer Part") "Q13FC1350000400") (field (name "Manufacturer") "EPSON(爱普生)"))
      (libsource (lib "easyedapro") (part "Q13FC1350000400"))
    )
  )
  (nets
    (net (code "1") (name "+1V5") (class "Default")
      (node (ref "C49") (pin "1") (pinfunction "1_1") (pintype "input"))
      (node (ref "C50") (pin "1") (pinfunction "1_1") (pintype "input"))
      (node (ref "C51") (pin "1") (pinfunction "1_1") (pintype "input"))
      (node (ref "FPC1") (pin "10") (pinfunction "DVDD_10") (pintype "input"))
      (node (ref "U19") (pin "6") (pinfunction "VOUT1_6") (pintype "input"))
    )
    (net (code "2") (name "+2V8") (class "Default")
      (node (ref "C47") (pin "2") (pinfunction "2_2") (pintype "input"))
      (node (ref "C48") (pin "2") (pinfunction "2_2") (pintype "input"))
      (node (ref "C52") (pin "2") (pinfunction "2_2") (pintype "input"))
      (node (ref "L6") (pin "2") (pinfunction "2_2") (pintype "input"))
      (node (ref "R57") (pin "2") (pinfunction "2_2") (pintype "input"))
      (node (ref "R58") (pin "2") (pinfunction "2_2") (pintype "input"))
    )
    (net (code "3") (name "0") (class "Default")
      (node (ref "C26") (pin "2") (pinfunction "2_2") (pintype "input"))
      (node (ref "Q1") (pin "2") (pinfunction "E_2") (pintype "input"))
      (node (ref "Q2") (pin "2") (pinfunction "E_2") (pintype "input"))
      (node (ref "Q3") (pin "2") (pinfunction "E_2") (pintype "input"))
      (node (ref "Q4") (pin "2") (pinfunction "E_2") (pintype "input"))
      (node (ref "R11") (pin "1") (pinfunction "1_1") (pintype "input"))
      (node (ref "R14") (pin "1") (pinfunction "1_1") (pintype "input"))
      (node (ref "R17") (pin "1") (pinfunction "1_1") (pintype "input"))
      (node (ref "R20") (pin "1") (pinfunction "1_1") (pintype "input"))
      (node (ref "U3") (pin "3") (pinfunction "EM_3") (pintype "input"))
      (node (ref "U4") (pin "3") (pinfunction "0V_3") (pintype "input"))
      (node (ref "U5") (pin "3") (pinfunction "EM_3") (pintype "input"))
      (node (ref "U6") (pin "3") (pinfunction "EM_3") (pintype "input"))
      (node (ref "U7") (pin "3") (pinfunction "EM_3") (pintype "input"))
    )
    (net (code "4") (name "CAMV") (class "Default")
      (node (ref "L6") (pin "1") (pinfunction "1_1") (pintype "input"))
      (node (ref "U19") (pin "4") (pinfunction "VOUT2_4") (pintype "input"))
    )
    (net (code "5") (name "CIN_1") (class "Default")
      (node (ref "CN5") (pin "5") (pinfunction "5_5") (pintype "input"))
      (node (ref "U14") (pin "6") (pinfunction "C1_IN_6") (pintype "input"))
    )
    (net (code "6") (name "CIN_2") (class "Default")
      (node (ref "CN5") (pin "7") (pinfunction "7_7") (pintype "input"))
      (node (ref "U14") (pin "8") (pinfunction "C2_IN_8") (pintype "input"))
    )
    (net (code "7") (name "CIN_3") (class "Default")
      (node (ref "CN5") (pin "9") (pinfunction "9_9") (pintype "input"))
      (node (ref "U14") (pin "10") (pinfunction "C3_IN_10") (pintype "input"))
    )
    (net (code "8") (name "CIN_4") (class "Default")
      (node (ref "CN5") (pin "4") (pinfunction "4_4") (pintype "input"))
      (node (ref "U14") (pin "5") (pinfunction "C4_IN_5") (pintype "input"))
    )
    (net (code "9") (name "COUT_1") (class "Default")
      (node (ref "CN5") (pin "6") (pinfunction "6_6") (pintype "input"))
      (node (ref "U14") (pin "7") (pinfunction "C1_OUT_7") (pintype "input"))
    )
    (net (code "10") (name "COUT_2") (class "Default")
      (node (ref "CN5") (pin "8") (pinfunction "8_8") (pintype "input"))
      (node (ref "U14") (pin "9") (pinfunction "C2_OUT_9") (pintype "input"))
    )
    (net (code "11") (name "COUT_3") (class "Default")
      (node (ref "CN5") (pin "10") (pinfunction "10_10") (pintype "input"))
      (node (ref "U14") (pin "11") (pinfunction "C3_OUT_11") (pintype "input"))
    )
    (net (code "12") (name "COUT_4") (class "Default")
      (node (ref "CN5") (pin "3") (pinfunction "3_3") (pintype "input"))
      (node (ref "U14") (pin "4") (pinfunction "C4_OUT_4") (pintype "input"))
    )
    (net (code "13") (name "CS") (class "Default")
      (node (ref "U13") (pin "1") (pinfunction "CS#_1") (pintype "input"))
      (node (ref "U17") (pin "33") (pinfunction "PB12_33") (pintype "input"))
    )
    (net (code "14") (name "C_CLK") (class "Default")
      (node (ref "FPC1") (pin "13") (pinfunction "XCLK_13") (pintype "input"))
      (node (ref "U17") (pin "30") (pinfunction "PB11_30") (pintype "input"))
    )
    (net (code "15") (name "C_HSYNC") (class "Default")
      (node (ref "FPC1") (pin "9") (pinfunction "HREF_9") (pintype "input"))
      (node (ref "U17") (pin "29") (pinfunction "PB10_29") (pintype "input"))
    )
    (net (code "16") (name "C_PCLK") (class "Default")
      (node (ref "FPC1") (pin "17") (pinfunction "PCLK_17") (pintype "input"))
      (node (ref "U17") (pin "39") (pinfunction "PC8_39") (pintype "input"))
    )
    (net (code "17") (name "C_PWDN") (class "Default")
      (node (ref "FPC1") (pin "8") (pinfunction "PWDN_8") (pintype "input"))
      (node (ref "R45") (pin "1") (pinfunction "1_1") (pintype "input"))
      (node (ref "U17") (pin "28") (pinfunction "PB2_28") (pintype "input"))
    )
    (net (code "18") (name "C_RST") (class "Default")
      (node (ref "FPC1") (pin "6") (pinfunction "RESET_6") (pintype "input"))
      (node (ref "R44") (pin "1") (pinfunction "1_1") (pintype "input"))
      (node (ref "U17") (pin "26") (pinfunction "PB0_26") (pintype "input"))
    )
    (net (code "19") (name "C_VSYNC") (class "Default")
      (node (ref "FPC1") (pin "7") (pinfunction "VSYNC_7") (pintype "input"))
      (node (ref "U17") (pin "27") (pinfunction "PB1_27") (pintype "input"))
    )
    (net (code "20") (name "DC") (class "Default")
      (node (ref "C1") (pin "2") (pinfunction "2_2") (pintype "input"))
      (node (ref "C24") (pin "2") (pinfunction "2_2") (pintype "input"))
      (node (ref "C25") (pin "2") (pinfunction "2_2") (pintype "input"))
      (node (ref "C3") (pin "2") (pinfunction "2_2") (pintype "input"))
      (node (ref "C4") (pin "2") (pinfunction "2_2") (pintype "input"))
      (node (ref "D7") (pin "1") (pinfunction "K_1") (pintype "input"))
      (node (ref "D8") (pin "1") (pinfunction "K_1") (pintype "input"))
      (node (ref "D9") (pin "1") (pinfunction "K_1") (pintype "input"))
      (node (ref "U21") (pin "3") (pinfunction "VIN_3") (pintype "input"))
      (node (ref "U4") (pin "2") (pinfunction "VIN_2") (pintype "input"))
    )
    (net (code "21") (name "D_DATA0") (class "Default")
      (node (ref "FPC1") (pin "19") (pinfunction "D2_19") (pintype "input"))
      (node (ref "U17") (pin "8") (pinfunction "PC0_8") (pintype "input"))
    )
    (net (code "22") (name "D_DATA1") (class "Default")
      (node (ref "FPC1") (pin "21") (pinfunction "D3_21") (pintype "input"))
      (node (ref "U17") (pin "9") (pinfunction "PC1_9") (pintype "input"))
    )
    (net (code "23") (name "D_DATA2") (class "Default")
      (node (ref "FPC1") (pin "22") (pinfunction "D4_22") (pintype "input"))
      (node (ref "U17") (pin "10") (pinfunction "PC2_10") (pintype "input"))
    )
    (net (code "24") (name "D_DATA3") (class "Default")
      (node (ref "FPC1") (pin "20") (pinfunction "D5_20") (pintype "input"))
      (node (ref "U17") (pin "11") (pinfunction "PC3_11") (pintype "input"))
    )
    (net (code "25") (name "D_DATA4") (class "Default")
      (node (ref "FPC1") (pin "18") (pinfunction "D6_18") (pintype "input"))
      (node (ref "U17") (pin "24") (pinfunction "PC4_24") (pintype "input"))
    )
    (net (code "26") (name "D_DATA5") (class "Default")
      (node (ref "FPC1") (pin "16") (pinfunction "D7_16") (pintype "input"))
      (node (ref "U17") (pin "25") (pinfunction "PC5_25") (pintype "input"))
    )
    (net (code "27") (name "D_DATA6") (class "Default")
      (node (ref "FPC1") (pin "14") (pinfunction "D8_14") (pintype "input"))
      (node (ref "U17") (pin "37") (pinfunction "PC6_37") (pintype "input"))
    )
    (net (code "28") (name "D_DATA7") (class "Default")
      (node (ref "FPC1") (pin "12") (pinfunction "D9_12") (pintype "input"))
      (node (ref "U17") (pin "38") (pinfunction "PC7_38") (pintype "input"))
    )
    (net (code "29") (name "GND") (class "Default")
      (node (ref "C1") (pin "1") (pinfunction "1_1") (pintype "input"))
      (node (ref "C11") (pin "1") (pinfunction "1_1") (pintype "input"))
      (node (ref "C16") (pin "1") (pinfunction "1_1") (pintype "input"))
      (node (ref "C24") (pin "1") (pinfunction "1_1") (pintype "input"))
      (node (ref "C25") (pin "1") (pinfunction "1_1") (pintype "input"))
      (node (ref "C28") (pin "2") (pinfunction "2_2") (pintype "input"))
      (node (ref "C29") (pin "2") (pinfunction "2_2") (pintype "input"))
      (node (ref "C3") (pin "1") (pinfunction "1_1") (pintype "input"))
      (node (ref "C30") (pin "2") (pinfunction "2_2") (pintype "input"))
      (node (ref "C31") (pin "2") (pinfunction "2_2") (pintype "input"))
      (node (ref "C32") (pin "2") (pinfunction "2_2") (pintype "input"))
      (node (ref "C33") (pin "1") (pinfunction "1_1") (pintype "input"))
      (node (ref "C34") (pin "1") (pinfunction "1_1") (pintype "input"))
      (node (ref "C35") (pin "1") (pinfunction "1_1") (pintype "input"))
      (node (ref "C36") (pin "1") (pinfunction "1_1") (pintype "input"))
      (node (ref "C37") (pin "1") (pinfunction "1_1") (pintype "input"))
      (node (ref "C38") (pin "2") (pinfunction "2_2") (pintype "input"))
      (node (ref "C39") (pin "2") (pinfunction "2_2") (pintype "input"))
      (node (ref "C4") (pin "1") (pinfunction "1_1") (pintype "input"))
      (node (ref "C40") (pin "1") (pinfunction "1_1") (pintype "input"))
      (node (ref "C43") (pin "2") (pinfunction "2_2") (pintype "input"))
      (node (ref "C45") (pin "1") (pinfunction "1_1") (pintype "input"))
      (node (ref "C46") (pin "1") (pinfunction "1_1") (pintype "input"))
      (node (ref "C47") (pin "1") (pinfunction "1_1") (pintype "input"))
      (node (ref "C48") (pin "1") (pinfunction "1_1") (pintype "input"))
      (node (ref "C49") (pin "2") (pinfunction "2_2") (pintype "input"))
      (node (ref "C50") (pin "2") (pinfunction "2_2") (pintype "input"))
      (node (ref "C51") (pin "2") (pinfunction "2_2") (pintype "input"))
      (node (ref "C52") (pin "1") (pinfunction "1_1") (pintype "input"))
      (node (ref "C53") (pin "2") (pinfunction "2_2") (pintype "input"))
      (node (ref "C54") (pin "1") (pinfunction "1_1") (pintype "input"))
      (node (ref "C55") (pin "1") (pinfunction "1_1") (pintype "input"))
      (node (ref "C56") (pin "2") (pinfunction "2_2") (pintype "input"))
      (node (ref "C6") (pin "1") (pinfunction "1_1") (pintype "input"))
      (node (ref "CN10") (pin "2") (pinfunction "2_2") (pintype "input"))
      (node (ref "CN11") (pin "10") (pinfunction "10_10") (pintype "input"))
      (node (ref "CN11") (pin "11") (pinfunction "11_11") (pintype "input"))
      (node (ref "CN11") (pin "12") (pinfunction "12_12") (pintype "input"))
      (node (ref "CN5") (pin "11") (pinfunction "11_11") (pintype "input"))
      (node (ref "CN5") (pin "12") (pinfunction "12_12") (pintype "input"))
      (node (ref "CN5") (pin "2") (pinfunction "2_2") (pintype "input"))
      (node (ref "DC1") (pin "2") (pinfunction "2_2") (pintype "input"))
      (node (ref "DC1") (pin "3") (pinfunction "3_3") (pintype "input"))
      (node (ref "FPC1") (pin "15") (pinfunction "DGND_15") (pintype "input"))
      (node (ref "FPC1") (pin "2") (pinfunction "AGND_2") (pintype "input"))
      (node (ref "FPC1") (pin "25") (pinfunction "NC_25") (pintype "input"))
      (node (ref "FPC1") (pin "26") (pinfunction "NC_26") (pintype "input"))
      (node (ref "H2") (pin "3") (pinfunction "3_3") (pintype "input"))
      (node (ref "LED5") (pin "1") (pinfunction "C_1") (pintype "input"))
      (node (ref "R1") (pin "2") (pinfunction "2_2") (pintype "input"))
      (node (ref "R2") (pin "2") (pinfunction "2_2") (pintype "input"))
      (node (ref "R21") (pin "1") (pinfunction "1_1") (pintype "input"))
      (node (ref "R50") (pin "2") (pinfunction "2_2") (pintype "input"))
      (node (ref "R51") (pin "2") (pinfunction "2_2") (pintype "input"))
      (node (ref "TP1") (pin "1") (pinfunction "1_1") (pintype "input"))
      (node (ref "TP2") (pin "1") (pinfunction "1_1") (pintype "input"))
      (node (ref "TP3") (pin "1") (pinfunction "1_1") (pintype "input"))
      (node (ref "TP4") (pin "1") (pinfunction "1_1") (pintype "input"))
      (node (ref "U13") (pin "4") (pinfunction "VSS_4") (pintype "input"))
      (node (ref "U14") (pin "13") (pinfunction "ADDR_13") (pintype "input"))
      (node (ref "U14") (pin "2") (pinfunction "MODE_2") (pintype "input"))
      (node (ref "U14") (pin "21") (pinfunction "EP_21") (pintype "input"))
      (node (ref "U14") (pin "3") (pinfunction "VSS_3") (pintype "input"))
      (node (ref "U17") (pin "12") (pinfunction "VSSA_12") (pintype "input"))
      (node (ref "U17") (pin "18") (pinfunction "VSS_4_18") (pintype "input"))
      (node (ref "U17") (pin "31") (pinfunction "VSS_1_31") (pintype "input"))
      (node (ref "U17") (pin "47") (pinfunction "VSS_2_47") (pintype "input"))
      (node (ref "U17") (pin "63") (pinfunction "VSS_3_63") (pintype "input"))
      (node (ref "U19") (pin "5") (pinfunction "VSS_5") (pintype "input"))
      (node (ref "U20") (pin "3") (pinfunction "GND_3") (pintype "input"))
      (node (ref "U21") (pin "1") (pinfunction "GND_1") (pintype "input"))
      (node (ref "U4") (pin "1") (pinfunction "GND_1") (pintype "input"))
      (node (ref "USB1") (pin "0") (pinfunction "EP_0") (pintype "input"))
      (node (ref "USB1") (pin "A1B12") (pinfunction "GND_A1B12") (pintype "input"))
      (node (ref "USB1") (pin "B1A12") (pinfunction "GND_B1A12") (pintype "input"))
      (node (ref "USB2") (pin "0") (pinfunction "EP_0") (pintype "input"))
      (node (ref "USB2") (pin "A1B12") (pinfunction "GND_A1B12") (pintype "input"))
      (node (ref "USB2") (pin "B1A12") (pinfunction "GND_B1A12") (pintype "input"))
    )
    (net (code "30") (name "IO_CTRL1") (class "Default")
      (node (ref "U17") (pin "20") (pinfunction "PA4_20") (pintype "input"))
      (node (ref "U3") (pin "2") (pinfunction "CAT_2") (pintype "input"))
    )
    (net (code "31") (name "IO_CTRL2") (class "Default")
      (node (ref "U17") (pin "21") (pinfunction "PA5_21") (pintype "input"))
      (node (ref "U5") (pin "2") (pinfunction "CAT_2") (pintype "input"))
    )
    (net (code "32") (name "IO_CTRL3") (class "Default")
      (node (ref "U17") (pin "22") (pinfunction "PA6_22") (pintype "input"))
      (node (ref "U6") (pin "2") (pinfunction "CAT_2") (pintype "input"))
    )
    (net (code "33") (name "IO_CTRL4") (class "Default")
      (node (ref "U17") (pin "23") (pinfunction "PA7_23") (pintype "input"))
      (node (ref "U7") (pin "2") (pinfunction "CAT_2") (pintype "input"))
    )
    (net (code "34") (name "LCD_BLK") (class "Default")
      (node (ref "CN11") (pin "7") (pinfunction "7_7") (pintype "input"))
      (node (ref "U17") (pin "17") (pinfunction "PA3_17") (pintype "input"))
    )
    (net (code "35") (name "LCD_CD") (class "Default")
      (node (ref "CN11") (pin "5") (pinfunction "5_5") (pintype "input"))
      (node (ref "U17") (pin "15") (pinfunction "PA1_15") (pintype "input"))
    )
    (net (code "36") (name "LCD_CS") (class "Default")
      (node (ref "CN11") (pin "4") (pinfunction "4_4") (pintype "input"))
      (node (ref "U17") (pin "14") (pinfunction "PA0_WAKRUP_14") (pintype "input"))
    )
    (net (code "37") (name "LCD_RST") (class "Default")
      (node (ref "CN11") (pin "6") (pinfunction "6_6") (pintype "input"))
      (node (ref "U17") (pin "16") (pinfunction "PA2_16") (pintype "input"))
    )
    (net (code "38") (name "LOAD") (class "Default")
      (node (ref "C26") (pin "1") (pinfunction "1_1") (pintype "input"))
      (node (ref "D1") (pin "1") (pinfunction "K_1") (pintype "input"))
      (node (ref "D2") (pin "1") (pinfunction "K_1") (pintype "input"))
      (node (ref "D3") (pin "1") (pinfunction "K_1") (pintype "input"))
      (node (ref "D4") (pin "1") (pinfunction "K_1") (pintype "input"))
      (node (ref "K1") (pin "1") (pinfunction "1_1") (pintype "input"))
      (node (ref "K2") (pin "1") (pinfunction "1_1") (pintype "input"))
      (node (ref "K3") (pin "1") (pinfunction "1_1") (pintype "input"))
      (node (ref "K4") (pin "1") (pinfunction "1_1") (pintype "input"))
      (node (ref "R10") (pin "2") (pinfunction "2_2") (pintype "input"))
      (node (ref "R13") (pin "2") (pinfunction "2_2") (pintype "input"))
      (node (ref "R16") (pin "2") (pinfunction "2_2") (pintype "input"))
      (node (ref "R19") (pin "2") (pinfunction "2_2") (pintype "input"))
      (node (ref "U4") (pin "4") (pinfunction "+VO_4") (pintype "input"))
    )
    (net (code "39") (name "MISO") (class "Default")
      (node (ref "CN11") (pin "3") (pinfunction "3_3") (pintype "input"))
      (node (ref "U13") (pin "2") (pinfunction "SO(IO1)_2") (pintype "input"))
      (node (ref "U17") (pin "35") (pinfunction "PB14_35") (pintype "input"))
    )
    (net (code "40") (name "MOSI") (class "Default")
      (node (ref "CN11") (pin "2") (pinfunction "2_2") (pintype "input"))
      (node (ref "U13") (pin "5") (pinfunction "SI(IO0)_5") (pintype "input"))
      (node (ref "U17") (pin "36") (pinfunction "PB15_36") (pintype "input"))
    )
    (net (code "41") (name "M_ALERT") (class "Default")
      (node (ref "U14") (pin "14") (pinfunction "ALERT_14") (pintype "input"))
      (node (ref "U17") (pin "56") (pinfunction "PB4_56") (pintype "input"))
    )
    (net (code "42") (name "M_C") (class "Default")
      (node (ref "R39") (pin "2") (pinfunction "2_2") (pintype "input"))
      (node (ref "U17") (pin "46") (pinfunction "PA13_46") (pintype "input"))
    )
    (net (code "43") (name "M_HX1") (class "Default")
      (node (ref "C33") (pin "2") (pinfunction "2_2") (pintype "input"))
      (node (ref "R27") (pin "1") (pinfunction "1_1") (pintype "input"))
      (node (ref "U12") (pin "2") (pinfunction "2_2") (pintype "input"))
      (node (ref "U17") (pin "5") (pinfunction "PD0_OSC32_IN_5") (pintype "input"))
    )
    (net (code "44") (name "M_HX2") (class "Default")
      (node (ref "C34") (pin "2") (pinfunction "2_2") (pintype "input"))
      (node (ref "R27") (pin "2") (pinfunction "2_2") (pintype "input"))
      (node (ref "U12") (pin "1") (pinfunction "1_1") (pintype "input"))
      (node (ref "U17") (pin "6") (pinfunction "PD1_OSC32_OUT_6") (pintype "input"))
    )
    (net (code "45") (name "M_LX1") (class "Default")
      (node (ref "C36") (pin "2") (pinfunction "2_2") (pintype "input"))
      (node (ref "U17") (pin "3") (pinfunction "PC14_OSC32_IN_3") (pintype "input"))
      (node (ref "X1") (pin "2") (pinfunction "2_2") (pintype "input"))
    )
    (net (code "46") (name "M_LX2") (class "Default")
      (node (ref "C37") (pin "2") (pinfunction "2_2") (pintype "input"))
      (node (ref "U17") (pin "4") (pinfunction "PC15_OSC32_OUT_4") (pintype "input"))
      (node (ref "X1") (pin "1") (pinfunction "1_1") (pintype "input"))
    )
    (net (code "47") (name "M_RST#") (class "Default")
      (node (ref "C28") (pin "1") (pinfunction "1_1") (pintype "input"))
      (node (ref "R22") (pin "1") (pinfunction "1_1") (pintype "input"))
      (node (ref "U17") (pin "7") (pinfunction "NRST_7") (pintype "input"))
    )
    (net (code "48") (name "M_SCL") (class "Default")
      (node (ref "FPC1") (pin "5") (pinfunction "SCL_5") (pintype "input"))
      (node (ref "R29") (pin "2") (pinfunction "2_2") (pintype "input"))
      (node (ref "U14") (pin "15") (pinfunction "SCL_15") (pintype "input"))
      (node (ref "U17") (pin "58") (pinfunction "PB6_58") (pintype "input"))
    )
    (net (code "49") (name "M_SDA") (class "Default")
      (node (ref "FPC1") (pin "3") (pinfunction "SDA_3") (pintype "input"))
      (node (ref "R28") (pin "1") (pinfunction "1_1") (pintype "input"))
      (node (ref "U14") (pin "12") (pinfunction "SDA/DQ_12") (pintype "input"))
      (node (ref "U17") (pin "59") (pinfunction "PB7_59") (pintype "input"))
    )
    (net (code "50") (name "Net-(D1-A)") (class "Default")
      (node (ref "D1") (pin "2") (pinfunction "A_2") (pintype "input"))
      (node (ref "K1") (pin "2") (pinfunction "2_2") (pintype "input"))
      (node (ref "Q1") (pin "3") (pinfunction "C_3") (pintype "input"))
    )
    (net (code "51") (name "Net-(D2-A)") (class "Default")
      (node (ref "D2") (pin "2") (pinfunction "A_2") (pintype "input"))
      (node (ref "K2") (pin "2") (pinfunction "2_2") (pintype "input"))
      (node (ref "Q2") (pin "3") (pinfunction "C_3") (pintype "input"))
    )
    (net (code "52") (name "Net-(D3-A)") (class "Default")
      (node (ref "D3") (pin "2") (pinfunction "A_2") (pintype "input"))
      (node (ref "K3") (pin "2") (pinfunction "2_2") (pintype "input"))
      (node (ref "Q3") (pin "3") (pinfunction "C_3") (pintype "input"))
    )
    (net (code "53") (name "Net-(D4-A)") (class "Default")
      (node (ref "D4") (pin "2") (pinfunction "A_2") (pintype "input"))
      (node (ref "K4") (pin "2") (pinfunction "2_2") (pintype "input"))
      (node (ref "Q4") (pin "3") (pinfunction "C_3") (pintype "input"))
    )
    (net (code "54") (name "Net-(D5-K)") (class "Default")
      (node (ref "C43") (pin "1") (pinfunction "1_1") (pintype "input"))
      (node (ref "D5") (pin "1") (pinfunction "K_1") (pintype "input"))
      (node (ref "D6") (pin "1") (pinfunction "K_1") (pintype "input"))
      (node (ref "U17") (pin "1") (pinfunction "VBAT_1") (pintype "input"))
    )
    (net (code "55") (name "Net-(D6-A)") (class "Default")
      (node (ref "CN10") (pin "1") (pinfunction "1_1") (pintype "input"))
      (node (ref "D6") (pin "2") (pinfunction "A_2") (pintype "input"))
    )
    (net (code "56") (name "Net-(D7-A)") (class "Default")
      (node (ref "D7") (pin "2") (pinfunction "A_2") (pintype "input"))
      (node (ref "DC1") (pin "4") (pinfunction "4_4") (pintype "input"))
    )
    (net (code "57") (name "Net-(D8-A)") (class "Default")
      (node (ref "D8") (pin "2") (pinfunction "A_2") (pintype "input"))
      (node (ref "USB2") (pin "A4B9") (pinfunction "VBUS_A4B9") (pintype "input"))
      (node (ref "USB2") (pin "B4A9") (pinfunction "VBUS_B4A9") (pintype "input"))
    )
    (net (code "58") (name "Net-(D9-A)") (class "Default")
      (node (ref "D9") (pin "2") (pinfunction "A_2") (pintype "input"))
      (node (ref "USB1") (pin "A4B9") (pinfunction "VBUS_A4B9") (pintype "input"))
      (node (ref "USB1") (pin "B4A9") (pinfunction "VBUS_B4A9") (pintype "input"))
    )
    (net (code "59") (name "Net-(FPC1-AVDD)") (class "Default")
      (node (ref "C56") (pin "1") (pinfunction "1_1") (pintype "input"))
      (node (ref "FPC1") (pin "4") (pinfunction "AVDD_4") (pintype "input"))
      (node (ref "R58") (pin "1") (pinfunction "1_1") (pintype "input"))
    )
    (net (code "60") (name "Net-(FPC1-DOVDD)") (class "Default")
      (node (ref "C55") (pin "2") (pinfunction "2_2") (pintype "input"))
      (node (ref "FPC1") (pin "11") (pinfunction "DOVDD_11") (pintype "input"))
      (node (ref "R57") (pin "1") (pinfunction "1_1") (pintype "input"))
    )
    (net (code "61") (name "Net-(H2-Pad1)") (class "Default")
      (node (ref "H2") (pin "1") (pinfunction "1_1") (pintype "input"))
      (node (ref "R38") (pin "1") (pinfunction "1_1") (pintype "input"))
    )
    (net (code "62") (name "Net-(H2-Pad4)") (class "Default")
      (node (ref "H2") (pin "4") (pinfunction "4_4") (pintype "input"))
      (node (ref "R39") (pin "1") (pinfunction "1_1") (pintype "input"))
    )
    (net (code "63") (name "Net-(LED2-A)") (class "Default")
      (node (ref "LED2") (pin "2") (pinfunction "A_2") (pintype "input"))
      (node (ref "R48") (pin "2") (pinfunction "2_2") (pintype "input"))
    )
    (net (code "64") (name "Net-(LED2-C)") (class "Default")
      (node (ref "LED2") (pin "1") (pinfunction "C_1") (pintype "input"))
      (node (ref "U17") (pin "51") (pinfunction "PC10_51") (pintype "input"))
    )
    (net (code "65") (name "Net-(LED3-A)") (class "Default")
      (node (ref "LED3") (pin "2") (pinfunction "A_2") (pintype "input"))
      (node (ref "R47") (pin "2") (pinfunction "2_2") (pintype "input"))
    )
    (net (code "66") (name "Net-(LED3-C)") (class "Default")
      (node (ref "LED3") (pin "1") (pinfunction "C_1") (pintype "input"))
      (node (ref "U17") (pin "52") (pinfunction "PC11_52") (pintype "input"))
    )
    (net (code "67") (name "Net-(LED4-A)") (class "Default")
      (node (ref "LED4") (pin "2") (pinfunction "A_2") (pintype "input"))
      (node (ref "R46") (pin "2") (pinfunction "2_2") (pintype "input"))
    )
    (net (code "68") (name "Net-(LED4-C)") (class "Default")
      (node (ref "LED4") (pin "1") (pinfunction "C_1") (pintype "input"))
      (node (ref "U17") (pin "53") (pinfunction "PC12_53") (pintype "input"))
    )
    (net (code "69") (name "Net-(LED5-A)") (class "Default")
      (node (ref "LED5") (pin "2") (pinfunction "A_2") (pintype "input"))
      (node (ref "R49") (pin "1") (pinfunction "1_1") (pintype "input"))
    )
    (net (code "70") (name "Net-(Q1-B)") (class "Default")
      (node (ref "Q1") (pin "1") (pinfunction "B_1") (pintype "input"))
      (node (ref "R10") (pin "1") (pinfunction "1_1") (pintype "input"))
      (node (ref "R11") (pin "2") (pinfunction "2_2") (pintype "input"))
      (node (ref "U3") (pin "4") (pinfunction "COL_4") (pintype "input"))
    )
    (net (code "71") (name "Net-(Q2-B)") (class "Default")
      (node (ref "Q2") (pin "1") (pinfunction "B_1") (pintype "input"))
      (node (ref "R13") (pin "1") (pinfunction "1_1") (pintype "input"))
      (node (ref "R14") (pin "2") (pinfunction "2_2") (pintype "input"))
      (node (ref "U5") (pin "4") (pinfunction "COL_4") (pintype "input"))
    )
    (net (code "72") (name "Net-(Q3-B)") (class "Default")
      (node (ref "Q3") (pin "1") (pinfunction "B_1") (pintype "input"))
      (node (ref "R16") (pin "1") (pinfunction "1_1") (pintype "input"))
      (node (ref "R17") (pin "2") (pinfunction "2_2") (pintype "input"))
      (node (ref "U6") (pin "4") (pinfunction "COL_4") (pintype "input"))
    )
    (net (code "73") (name "Net-(Q4-B)") (class "Default")
      (node (ref "Q4") (pin "1") (pinfunction "B_1") (pintype "input"))
      (node (ref "R19") (pin "1") (pinfunction "1_1") (pintype "input"))
      (node (ref "R20") (pin "2") (pinfunction "2_2") (pintype "input"))
      (node (ref "U7") (pin "4") (pinfunction "COL_4") (pintype "input"))
    )
    (net (code "74") (name "Net-(U3-AN)") (class "Default")
      (node (ref "R9") (pin "2") (pinfunction "2_2") (pintype "input"))
      (node (ref "U3") (pin "1") (pinfunction "AN_1") (pintype "input"))
    )
    (net (code "75") (name "Net-(U5-AN)") (class "Default")
      (node (ref "R12") (pin "2") (pinfunction "2_2") (pintype "input"))
      (node (ref "U5") (pin "1") (pinfunction "AN_1") (pintype "input"))
    )
    (net (code "76") (name "Net-(U6-AN)") (class "Default")
      (node (ref "R15") (pin "2") (pinfunction "2_2") (pintype "input"))
      (node (ref "U6") (pin "1") (pinfunction "AN_1") (pintype "input"))
    )
    (net (code "77") (name "Net-(U7-AN)") (class "Default")
      (node (ref "R18") (pin "2") (pinfunction "2_2") (pintype "input"))
      (node (ref "U7") (pin "1") (pinfunction "AN_1") (pintype "input"))
    )
    (net (code "78") (name "Net-(U17-BOOT0)") (class "Default")
      (node (ref "R21") (pin "2") (pinfunction "2_2") (pintype "input"))
      (node (ref "U17") (pin "60") (pinfunction "BOOT0_60") (pintype "input"))
    )
    (net (code "79") (name "Net-(U17-PA14)") (class "Default")
      (node (ref "R38") (pin "2") (pinfunction "2_2") (pintype "input"))
      (node (ref "U17") (pin "49") (pinfunction "PA14_49") (pintype "input"))
    )
    (net (code "80") (name "Net-(U20-RXD)") (class "Default")
      (node (ref "R56") (pin "1") (pinfunction "1_1") (pintype "input"))
      (node (ref "U20") (pin "9") (pinfunction "RXD_9") (pintype "input"))
    )
    (net (code "81") (name "Net-(U20-TXD)") (class "Default")
      (node (ref "R55") (pin "1") (pinfunction "1_1") (pintype "input"))
      (node (ref "U20") (pin "8") (pinfunction "TXD_8") (pintype "input"))
    )
    (net (code "82") (name "Net-(USB1-CC1)") (class "Default")
      (node (ref "R2") (pin "1") (pinfunction "1_1") (pintype "input"))
      (node (ref "USB1") (pin "A5") (pinfunction "CC1_A5") (pintype "input"))
    )
    (net (code "83") (name "Net-(USB1-CC2)") (class "Default")
      (node (ref "R1") (pin "1") (pinfunction "1_1") (pintype "input"))
      (node (ref "USB1") (pin "B5") (pinfunction "CC2_B5") (pintype "input"))
    )
    (net (code "84") (name "Net-(USB1-DN1)") (class "Default")
      (node (ref "R3") (pin "1") (pinfunction "1_1") (pintype "input"))
      (node (ref "USB1") (pin "A7") (pinfunction "DN1_A7") (pintype "input"))
      (node (ref "USB1") (pin "B7") (pinfunction "DN2_B7") (pintype "input"))
    )
    (net (code "85") (name "Net-(USB1-DP1)") (class "Default")
      (node (ref "R4") (pin "1") (pinfunction "1_1") (pintype "input"))
      (node (ref "R54") (pin "1") (pinfunction "1_1") (pintype "input"))
      (node (ref "USB1") (pin "A6") (pinfunction "DP1_A6") (pintype "input"))
      (node (ref "USB1") (pin "B6") (pinfunction "DP2_B6") (pintype "input"))
    )
    (net (code "86") (name "Net-(USB2-CC1)") (class "Default")
      (node (ref "R51") (pin "1") (pinfunction "1_1") (pintype "input"))
      (node (ref "USB2") (pin "A5") (pinfunction "CC1_A5") (pintype "input"))
    )
    (net (code "87") (name "Net-(USB2-CC2)") (class "Default")
      (node (ref "R50") (pin "1") (pinfunction "1_1") (pintype "input"))
      (node (ref "USB2") (pin "B5") (pinfunction "CC2_B5") (pintype "input"))
    )
    (net (code "88") (name "Net-(USB2-DN1)") (class "Default")
      (node (ref "R53") (pin "1") (pinfunction "1_1") (pintype "input"))
      (node (ref "USB2") (pin "A7") (pinfunction "DN1_A7") (pintype "input"))
      (node (ref "USB2") (pin "B7") (pinfunction "DN2_B7") (pintype "input"))
    )
    (net (code "89") (name "Net-(USB2-DP1)") (class "Default")
      (node (ref "R52") (pin "1") (pinfunction "1_1") (pintype "input"))
      (node (ref "USB2") (pin "A6") (pinfunction "DP1_A6") (pintype "input"))
      (node (ref "USB2") (pin "B6") (pinfunction "DP2_B6") (pintype "input"))
    )
    (net (code "90") (name "OC1A") (class "Default")
      (node (ref "CN1") (pin "1") (pinfunction "1_1") (pintype "input"))
      (node (ref "K1") (pin "3") (pinfunction "3_3") (pintype "input"))
    )
    (net (code "91") (name "OC1B") (class "Default")
      (node (ref "CN1") (pin "2") (pinfunction "2_2") (pintype "input"))
      (node (ref "K1") (pin "4") (pinfunction "4_4") (pintype "input"))
    )
    (net (code "92") (name "OC2A") (class "Default")
      (node (ref "CN2") (pin "1") (pinfunction "1_1") (pintype "input"))
      (node (ref "K2") (pin "3") (pinfunction "3_3") (pintype "input"))
    )
    (net (code "93") (name "OC2B") (class "Default")
      (node (ref "CN2") (pin "2") (pinfunction "2_2") (pintype "input"))
      (node (ref "K2") (pin "4") (pinfunction "4_4") (pintype "input"))
    )
    (net (code "94") (name "OC3A") (class "Default")
      (node (ref "CN3") (pin "1") (pinfunction "1_1") (pintype "input"))
      (node (ref "K3") (pin "3") (pinfunction "3_3") (pintype "input"))
    )
    (net (code "95") (name "OC3B") (class "Default")
      (node (ref "CN3") (pin "2") (pinfunction "2_2") (pintype "input"))
      (node (ref "K3") (pin "4") (pinfunction "4_4") (pintype "input"))
    )
    (net (code "96") (name "OC4A") (class "Default")
      (node (ref "CN4") (pin "1") (pinfunction "1_1") (pintype "input"))
      (node (ref "K4") (pin "3") (pinfunction "3_3") (pintype "input"))
    )
    (net (code "97") (name "OC4B") (class "Default")
      (node (ref "CN4") (pin "2") (pinfunction "2_2") (pintype "input"))
      (node (ref "K4") (pin "4") (pinfunction "4_4") (pintype "input"))
    )
    (net (code "98") (name "SCK") (class "Default")
      (node (ref "CN11") (pin "1") (pinfunction "1_1") (pintype "input"))
      (node (ref "U13") (pin "6") (pinfunction "SCLK_6") (pintype "input"))
      (node (ref "U17") (pin "34") (pinfunction "PB13_34") (pintype "input"))
    )
    (net (code "99") (name "S_RESET#") (class "Default")
      (node (ref "U14") (pin "1") (pinfunction "RSTN_1") (pintype "input"))
      (node (ref "U17") (pin "57") (pinfunction "PB5_57") (pintype "input"))
    )
    (net (code "100") (name "USART_RXD") (class "Default")
      (node (ref "R55") (pin "2") (pinfunction "2_2") (pintype "input"))
      (node (ref "U17") (pin "43") (pinfunction "PA10_43") (pintype "input"))
    )
    (net (code "101") (name "USART_TXD") (class "Default")
      (node (ref "R56") (pin "2") (pinfunction "2_2") (pintype "input"))
      (node (ref "U17") (pin "42") (pinfunction "PA9_42") (pintype "input"))
    )
    (net (code "102") (name "USB_CTRL") (class "Default")
      (node (ref "R54") (pin "2") (pinfunction "2_2") (pintype "input"))
      (node (ref "U17") (pin "41") (pinfunction "PA8_41") (pintype "input"))
    )
    (net (code "103") (name "USB_DN1") (class "Default")
      (node (ref "R3") (pin "2") (pinfunction "2_2") (pintype "input"))
      (node (ref "U17") (pin "44") (pinfunction "PA11_44") (pintype "input"))
    )
    (net (code "104") (name "USB_DN2") (class "Default")
      (node (ref "R53") (pin "2") (pinfunction "2_2") (pintype "input"))
      (node (ref "U20") (pin "2") (pinfunction "UD-_2") (pintype "input"))
    )
    (net (code "105") (name "USB_DP1") (class "Default")
      (node (ref "R4") (pin "2") (pinfunction "2_2") (pintype "input"))
      (node (ref "U17") (pin "45") (pinfunction "PA12_45") (pintype "input"))
    )
    (net (code "106") (name "USB_DP2") (class "Default")
      (node (ref "R52") (pin "2") (pinfunction "2_2") (pintype "input"))
      (node (ref "U20") (pin "1") (pinfunction "UD+_1") (pintype "input"))
    )
    (net (code "107") (name "VDD") (class "Default")
      (node (ref "C11") (pin "2") (pinfunction "2_2") (pintype "input"))
      (node (ref "C29") (pin "1") (pinfunction "1_1") (pintype "input"))
      (node (ref "C30") (pin "1") (pinfunction "1_1") (pintype "input"))
      (node (ref "C31") (pin "1") (pinfunction "1_1") (pintype "input"))
      (node (ref "C32") (pin "1") (pinfunction "1_1") (pintype "input"))
      (node (ref "C35") (pin "2") (pinfunction "2_2") (pintype "input"))
      (node (ref "C38") (pin "1") (pinfunction "1_1") (pintype "input"))
      (node (ref "C39") (pin "1") (pinfunction "1_1") (pintype "input"))
      (node (ref "C40") (pin "2") (pinfunction "2_2") (pintype "input"))
      (node (ref "C45") (pin "2") (pinfunction "2_2") (pintype "input"))
      (node (ref "C46") (pin "2") (pinfunction "2_2") (pintype "input"))
      (node (ref "C53") (pin "1") (pinfunction "1_1") (pintype "input"))
      (node (ref "C54") (pin "2") (pinfunction "2_2") (pintype "input"))
      (node (ref "C6") (pin "2") (pinfunction "2_2") (pintype "input"))
      (node (ref "CN11") (pin "9") (pinfunction "9_9") (pintype "input"))
      (node (ref "CN5") (pin "1") (pinfunction "1_1") (pintype "input"))
      (node (ref "D5") (pin "2") (pinfunction "A_2") (pintype "input"))
      (node (ref "H2") (pin "2") (pinfunction "2_2") (pintype "input"))
      (node (ref "L4") (pin "1") (pinfunction "1_1") (pintype "input"))
      (node (ref "R12") (pin "1") (pinfunction "1_1") (pintype "input"))
      (node (ref "R15") (pin "1") (pinfunction "1_1") (pintype "input"))
      (node (ref "R18") (pin "1") (pinfunction "1_1") (pintype "input"))
      (node (ref "R22") (pin "2") (pinfunction "2_2") (pintype "input"))
      (node (ref "R28") (pin "2") (pinfunction "2_2") (pintype "input"))
      (node (ref "R29") (pin "1") (pinfunction "1_1") (pintype "input"))
      (node (ref "R44") (pin "2") (pinfunction "2_2") (pintype "input"))
      (node (ref "R45") (pin "2") (pinfunction "2_2") (pintype "input"))
      (node (ref "R46") (pin "1") (pinfunction "1_1") (pintype "input"))
      (node (ref "R47") (pin "1") (pinfunction "1_1") (pintype "input"))
      (node (ref "R48") (pin "1") (pinfunction "1_1") (pintype "input"))
      (node (ref "R49") (pin "2") (pinfunction "2_2") (pintype "input"))
      (node (ref "R9") (pin "1") (pinfunction "1_1") (pintype "input"))
      (node (ref "U13") (pin "3") (pinfunction "WP#(IO2)_3") (pintype "input"))
      (node (ref "U13") (pin "7") (pinfunction "HOLD#(IO3)_7") (pintype "input"))
      (node (ref "U13") (pin "8") (pinfunction "VCC_8") (pintype "input"))
      (node (ref "U14") (pin "20") (pinfunction "VDD_20") (pintype "input"))
      (node (ref "U17") (pin "19") (pinfunction "VDD_4_19") (pintype "input"))
      (node (ref "U17") (pin "32") (pinfunction "VDD_1_32") (pintype "input"))
      (node (ref "U17") (pin "48") (pinfunction "VDD_2_48") (pintype "input"))
      (node (ref "U17") (pin "64") (pinfunction "VDD_3_64") (pintype "input"))
      (node (ref "U19") (pin "1") (pinfunction "EN1_1") (pintype "input"))
      (node (ref "U19") (pin "2") (pinfunction "VIN_2") (pintype "input"))
      (node (ref "U19") (pin "3") (pinfunction "EN2_3") (pintype "input"))
      (node (ref "U20") (pin "10") (pinfunction "V3_10") (pintype "input"))
      (node (ref "U20") (pin "7") (pinfunction "VCC_7") (pintype "input"))
      (node (ref "U21") (pin "2") (pinfunction "VOUT_2") (pintype "input"))
      (node (ref "U21") (pin "4") (pinfunction "VOUT_4") (pintype "input"))
    )
    (net (code "108") (name "VDDA") (class "Default")
      (node (ref "C16") (pin "2") (pinfunction "2_2") (pintype "input"))
      (node (ref "L4") (pin "2") (pinfunction "2_2") (pintype "input"))
      (node (ref "U17") (pin "13") (pinfunction "VDDA_13") (pintype "input"))
    )
    (net (code "109") (name "unconnected-(CN11-Pad8)") (class "Default")
      (node (ref "CN11") (pin "8") (pinfunction "8_8") (pintype "input+no_connect"))
    )
    (net (code "110") (name "unconnected-(FPC1-D0-Pad24)") (class "Default")
      (node (ref "FPC1") (pin "24") (pinfunction "D0_24") (pintype "input+no_connect"))
    )
    (net (code "111") (name "unconnected-(FPC1-D1-Pad23)") (class "Default")
      (node (ref "FPC1") (pin "23") (pinfunction "D1_23") (pintype "input+no_connect"))
    )
    (net (code "112") (name "unconnected-(FPC1-STROSE-Pad1)") (class "Default")
      (node (ref "FPC1") (pin "1") (pinfunction "STROSE_1") (pintype "input+no_connect"))
    )
    (net (code "113") (name "unconnected-(U14-NC-Pad16)") (class "Default")
      (node (ref "U14") (pin "16") (pinfunction "NC_16") (pintype "input+no_connect"))
    )
    (net (code "114") (name "unconnected-(U14-NC-Pad17)") (class "Default")
      (node (ref "U14") (pin "17") (pinfunction "NC_17") (pintype "input+no_connect"))
    )
    (net (code "115") (name "unconnected-(U14-NC-Pad18)") (class "Default")
      (node (ref "U14") (pin "18") (pinfunction "NC_18") (pintype "input+no_connect"))
    )
    (net (code "116") (name "unconnected-(U14-NC-Pad19)") (class "Default")
      (node (ref "U14") (pin "19") (pinfunction "NC_19") (pintype "input+no_connect"))
    )
    (net (code "117") (name "unconnected-(U17-PA15-Pad50)") (class "Default")
      (node (ref "U17") (pin "50") (pinfunction "PA15_50") (pintype "input+no_connect"))
    )
    (net (code "118") (name "unconnected-(U17-PB3-Pad55)") (class "Default")
      (node (ref "U17") (pin "55") (pinfunction "PB3_55") (pintype "input+no_connect"))
    )
    (net (code "119") (name "unconnected-(U17-PB8-Pad61)") (class "Default")
      (node (ref "U17") (pin "61") (pinfunction "PB8_61") (pintype "input+no_connect"))
    )
    (net (code "120") (name "unconnected-(U17-PB9-Pad62)") (class "Default")
      (node (ref "U17") (pin "62") (pinfunction "PB9_62") (pintype "input+no_connect"))
    )
    (net (code "121") (name "unconnected-(U17-PC9-Pad40)") (class "Default")
      (node (ref "U17") (pin "40") (pinfunction "PC9_40") (pintype "input+no_connect"))
    )
    (net (code "122") (name "unconnected-(U17-PC13_TAMPER_RTC-Pad2)") (class "Default")
      (node (ref "U17") (pin "2") (pinfunction "PC13_TAMPER_RTC_2") (pintype "input+no_connect"))
    )
    (net (code "123") (name "unconnected-(U17-PD2-Pad54)") (class "Default")
      (node (ref "U17") (pin "54") (pinfunction "PD2_54") (pintype "input+no_connect"))
    )
    (net (code "124") (name "unconnected-(U20-CTS#-Pad5)") (class "Default")
      (node (ref "U20") (pin "5") (pinfunction "CTS#_5") (pintype "input+no_connect"))
    )
    (net (code "125") (name "unconnected-(U20-RTS#-Pad4)") (class "Default")
      (node (ref "U20") (pin "4") (pinfunction "RTS#_4") (pintype "input+no_connect"))
    )
    (net (code "126") (name "unconnected-(U20-TNOW-Pad6)") (class "Default")
      (node (ref "U20") (pin "6") (pinfunction "TNOW_6") (pintype "input+no_connect"))
    )
    (net (code "127") (name "unconnected-(USB1-SBU1-PadA8)") (class "Default")
      (node (ref "USB1") (pin "A8") (pinfunction "SBU1_A8") (pintype "input+no_connect"))
    )
    (net (code "128") (name "unconnected-(USB1-SBU2-PadB8)") (class "Default")
      (node (ref "USB1") (pin "B8") (pinfunction "SBU2_B8") (pintype "input+no_connect"))
    )
    (net (code "129") (name "unconnected-(USB2-SBU1-PadA8)") (class "Default")
      (node (ref "USB2") (pin "A8") (pinfunction "SBU1_A8") (pintype "input+no_connect"))
    )
    (net (code "130") (name "unconnected-(USB2-SBU2-PadB8)") (class "Default")
      (node (ref "USB2") (pin "B8") (pinfunction "SBU2_B8") (pintype "input+no_connect"))
    )
  )
)
